# Eagle_LEDCUBE1.net
KiCad netlist of a schematic drawn in EAGLE
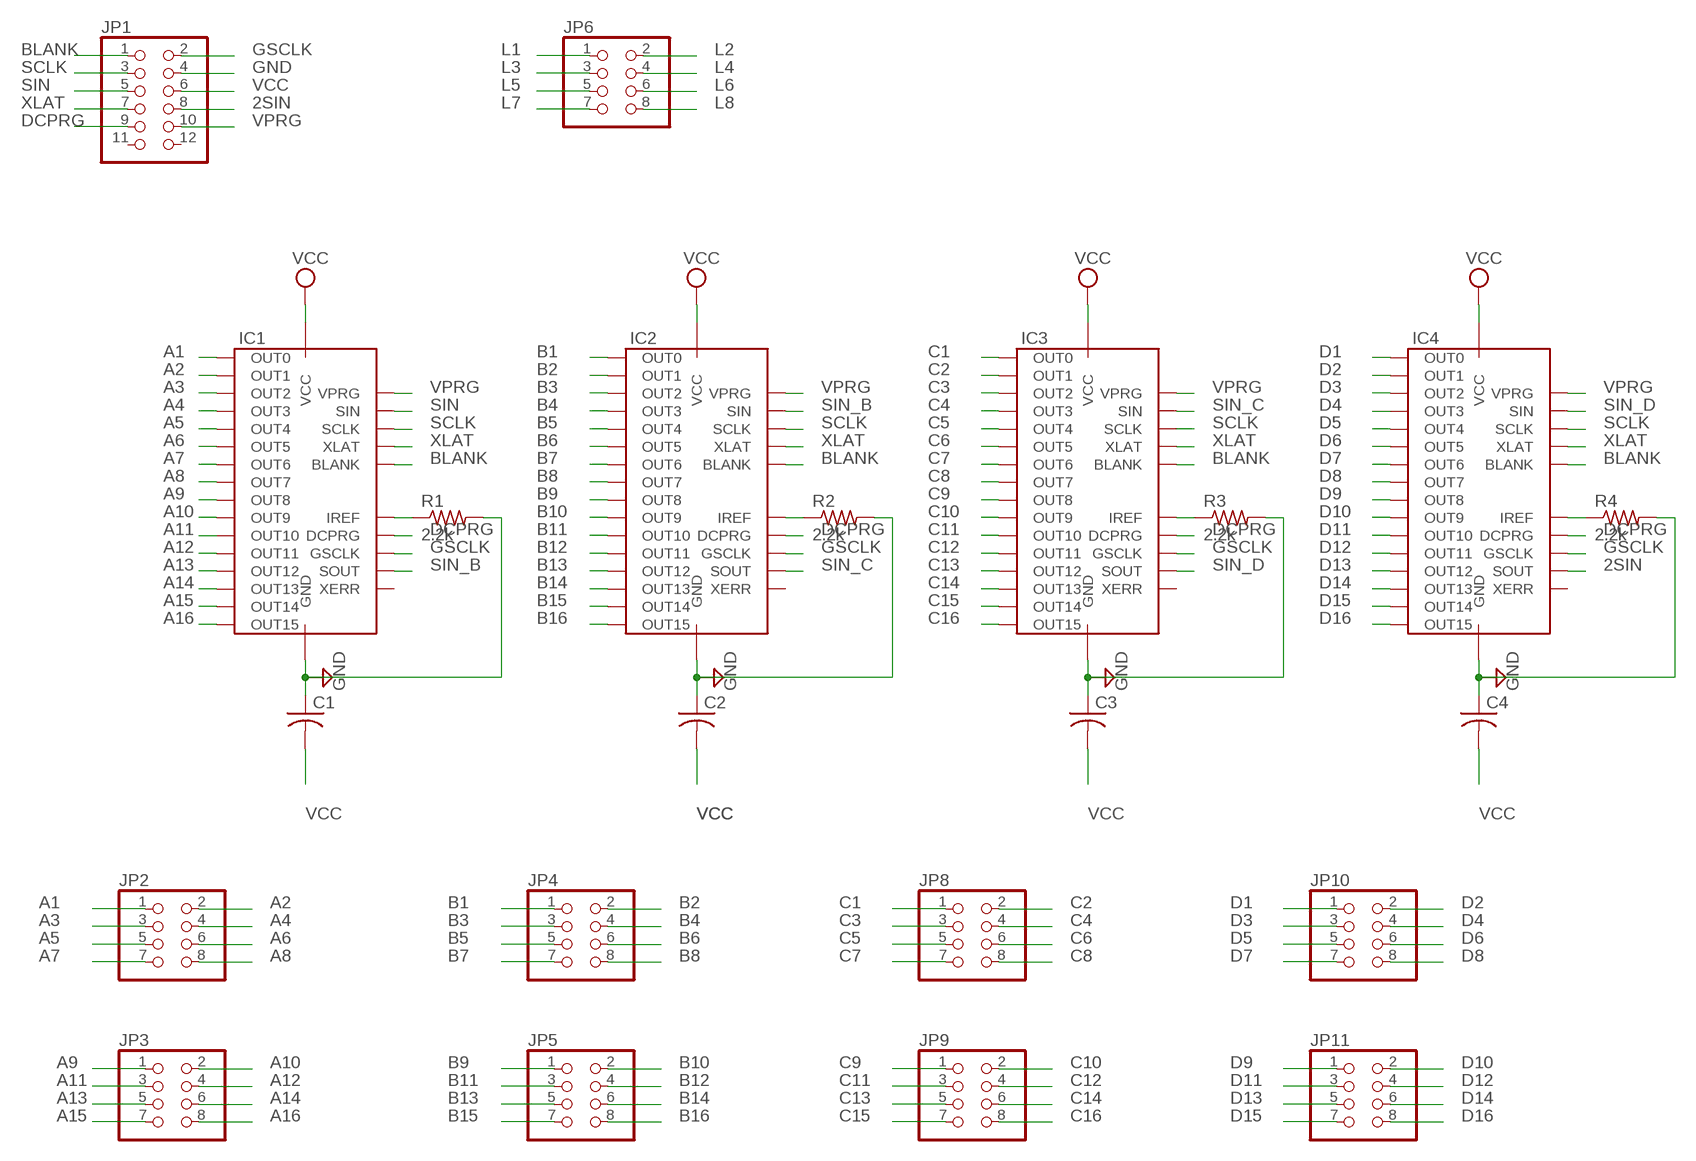
[diagram p0: schematic, sheet 1]
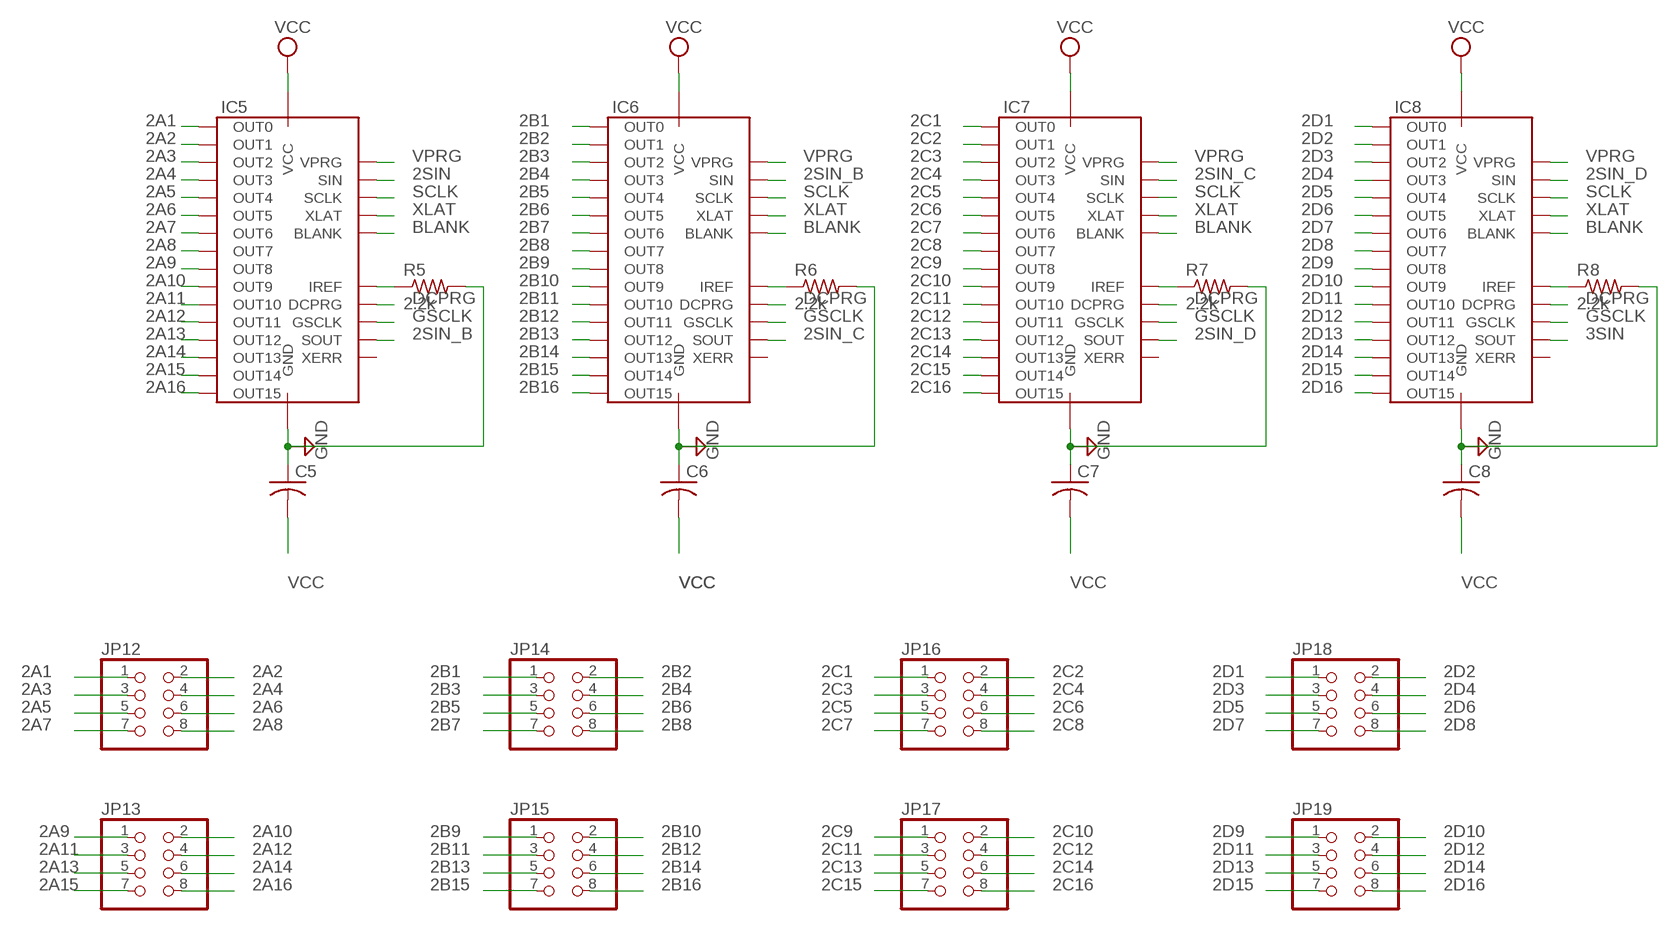
[diagram p1: schematic, sheet 2]
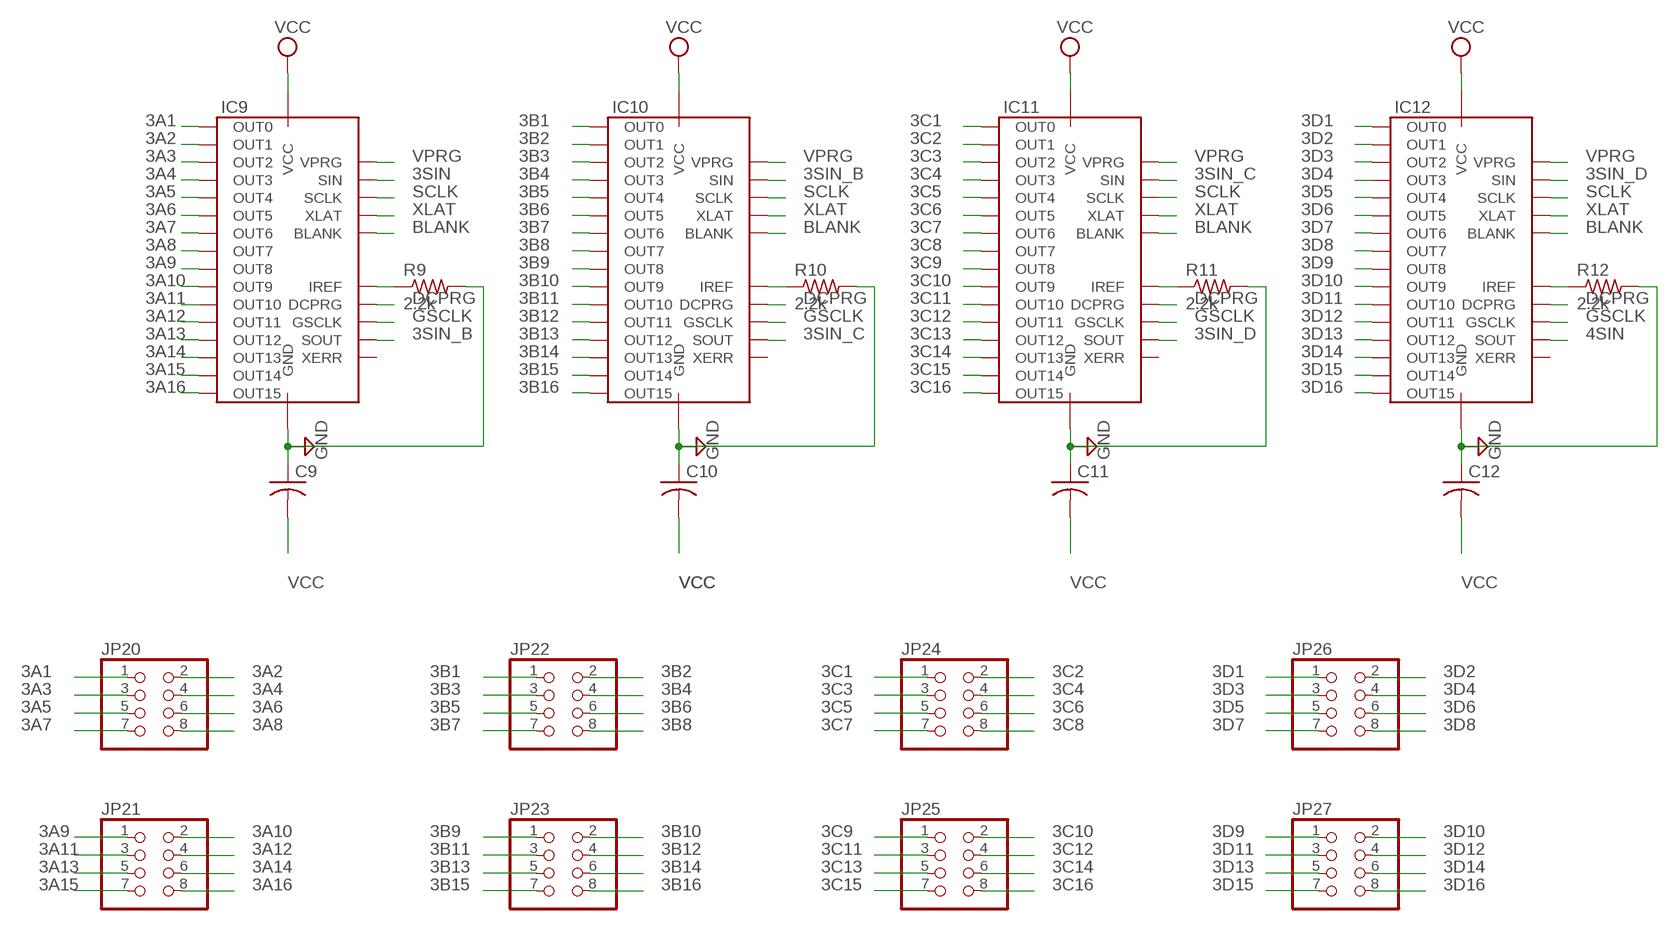
[diagram p2: schematic, sheet 3]
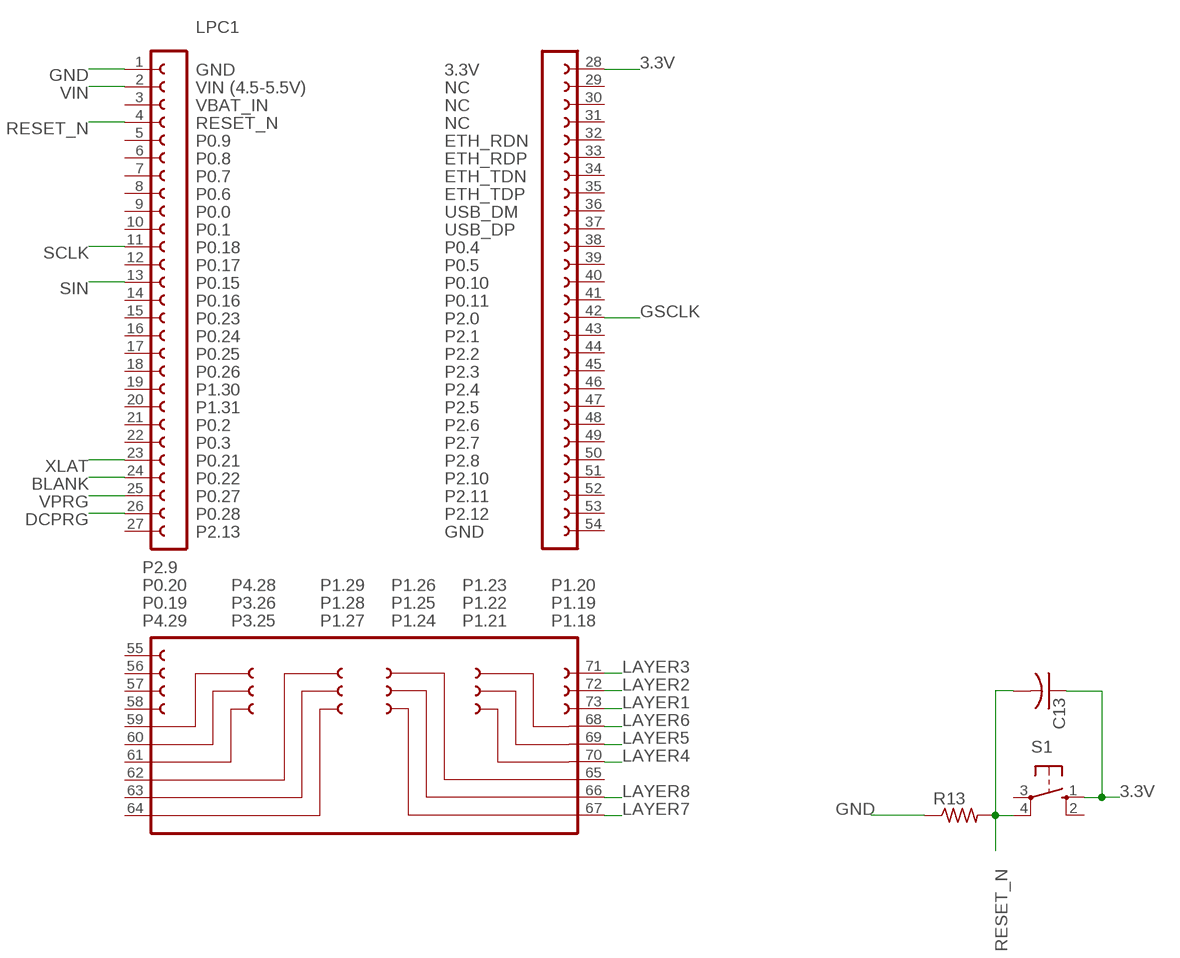
[diagram p3: schematic, sheet 4]
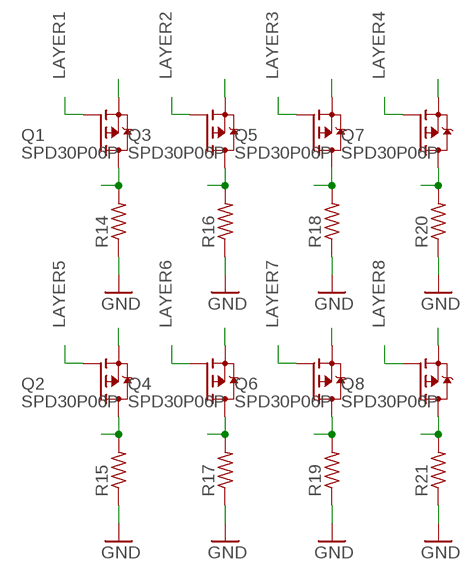
[diagram p4: schematic, sheet 5]

(export (version "E")
  (design (tool "Eeschema 10.0.6"))
  (components
    (comp (ref "C5")
      (value "C-USC0805K")
      (footprint "eagle-import:C0805K")
      (libsource (lib "eagle-import") (part "resistor_C-USC0805K"))
    )
    (comp (ref "C6")
      (value "C-USC0805K")
      (footprint "eagle-import:C0805K")
      (libsource (lib "eagle-import") (part "resistor_C-USC0805K"))
    )
    (comp (ref "C7")
      (value "C-USC0805K")
      (footprint "eagle-import:C0805K")
      (libsource (lib "eagle-import") (part "resistor_C-USC0805K"))
    )
    (comp (ref "C8")
      (value "C-USC0805K")
      (footprint "eagle-import:C0805K")
      (libsource (lib "eagle-import") (part "resistor_C-USC0805K"))
    )
    (comp (ref "IC5")
      (value "IC-PACKAGE_DIL28-1")
      (footprint "eagle-import:IC-SSOP28")
      (libsource (lib "eagle-import") (part "IC-PACKAGE_DIL28-1"))
    )
    (comp (ref "IC6")
      (value "IC-PACKAGE_DIL28-1")
      (footprint "eagle-import:IC-SSOP28")
      (libsource (lib "eagle-import") (part "IC-PACKAGE_DIL28-1"))
    )
    (comp (ref "IC7")
      (value "IC-PACKAGE_DIL28-1")
      (footprint "eagle-import:IC-SSOP28")
      (libsource (lib "eagle-import") (part "IC-PACKAGE_DIL28-1"))
    )
    (comp (ref "IC8")
      (value "IC-PACKAGE_DIL28-1")
      (footprint "eagle-import:IC-SSOP28")
      (libsource (lib "eagle-import") (part "IC-PACKAGE_DIL28-1"))
    )
    (comp (ref "JP12")
      (value "PINHD-2X4")
      (footprint "eagle-import:2X04")
      (libsource (lib "eagle-import") (part "PINHD-2X4"))
    )
    (comp (ref "JP13")
      (value "PINHD-2X4")
      (footprint "eagle-import:2X04")
      (libsource (lib "eagle-import") (part "PINHD-2X4"))
    )
    (comp (ref "JP14")
      (value "PINHD-2X4")
      (footprint "eagle-import:2X04")
      (libsource (lib "eagle-import") (part "PINHD-2X4"))
    )
    (comp (ref "JP15")
      (value "PINHD-2X4")
      (footprint "eagle-import:2X04")
      (libsource (lib "eagle-import") (part "PINHD-2X4"))
    )
    (comp (ref "JP16")
      (value "PINHD-2X4")
      (footprint "eagle-import:2X04")
      (libsource (lib "eagle-import") (part "PINHD-2X4"))
    )
    (comp (ref "JP17")
      (value "PINHD-2X4")
      (footprint "eagle-import:2X04")
      (libsource (lib "eagle-import") (part "PINHD-2X4"))
    )
    (comp (ref "JP18")
      (value "PINHD-2X4")
      (footprint "eagle-import:2X04")
      (libsource (lib "eagle-import") (part "PINHD-2X4"))
    )
    (comp (ref "JP19")
      (value "PINHD-2X4")
      (footprint "eagle-import:2X04")
      (libsource (lib "eagle-import") (part "PINHD-2X4"))
    )
    (comp (ref "R5")
      (value "2.2k")
      (footprint "eagle-import:R0805")
      (libsource (lib "eagle-import") (part "resistor_R-US_R0805"))
    )
    (comp (ref "R6")
      (value "2.2k")
      (footprint "eagle-import:R0805")
      (libsource (lib "eagle-import") (part "resistor_R-US_R0805"))
    )
    (comp (ref "R7")
      (value "2.2k")
      (footprint "eagle-import:R0805")
      (libsource (lib "eagle-import") (part "resistor_R-US_R0805"))
    )
    (comp (ref "R8")
      (value "2.2k")
      (footprint "eagle-import:R0805")
      (libsource (lib "eagle-import") (part "resistor_R-US_R0805"))
    )
    (comp (ref "Q1")
      (value "SPD30P06P")
      (footprint "eagle-import:TO251AA")
      (libsource (lib "eagle-import") (part "SPD30P06P"))
    )
    (comp (ref "Q2")
      (value "SPD30P06P")
      (footprint "eagle-import:TO251AA")
      (libsource (lib "eagle-import") (part "SPD30P06P"))
    )
    (comp (ref "Q3")
      (value "SPD30P06P")
      (footprint "eagle-import:TO251AA")
      (libsource (lib "eagle-import") (part "SPD30P06P"))
    )
    (comp (ref "Q4")
      (value "SPD30P06P")
      (footprint "eagle-import:TO251AA")
      (libsource (lib "eagle-import") (part "SPD30P06P"))
    )
    (comp (ref "Q5")
      (value "SPD30P06P")
      (footprint "eagle-import:TO251AA")
      (libsource (lib "eagle-import") (part "SPD30P06P"))
    )
    (comp (ref "Q6")
      (value "SPD30P06P")
      (footprint "eagle-import:TO251AA")
      (libsource (lib "eagle-import") (part "SPD30P06P"))
    )
    (comp (ref "Q7")
      (value "SPD30P06P")
      (footprint "eagle-import:TO251AA")
      (libsource (lib "eagle-import") (part "SPD30P06P"))
    )
    (comp (ref "Q8")
      (value "SPD30P06P")
      (footprint "eagle-import:TO251AA")
      (libsource (lib "eagle-import") (part "SPD30P06P"))
    )
    (comp (ref "R14")
      (value "R-US_R0805")
      (footprint "eagle-import:R0805")
      (libsource (lib "eagle-import") (part "resistor_R-US_R0805"))
    )
    (comp (ref "R15")
      (value "R-US_R0805")
      (footprint "eagle-import:R0805")
      (libsource (lib "eagle-import") (part "resistor_R-US_R0805"))
    )
    (comp (ref "R16")
      (value "R-US_R0805")
      (footprint "eagle-import:R0805")
      (libsource (lib "eagle-import") (part "resistor_R-US_R0805"))
    )
    (comp (ref "R17")
      (value "R-US_R0805")
      (footprint "eagle-import:R0805")
      (libsource (lib "eagle-import") (part "resistor_R-US_R0805"))
    )
    (comp (ref "R18")
      (value "R-US_R0805")
      (footprint "eagle-import:R0805")
      (libsource (lib "eagle-import") (part "resistor_R-US_R0805"))
    )
    (comp (ref "R19")
      (value "R-US_R0805")
      (footprint "eagle-import:R0805")
      (libsource (lib "eagle-import") (part "resistor_R-US_R0805"))
    )
    (comp (ref "R20")
      (value "R-US_R0805")
      (footprint "eagle-import:R0805")
      (libsource (lib "eagle-import") (part "resistor_R-US_R0805"))
    )
    (comp (ref "R21")
      (value "R-US_R0805")
      (footprint "eagle-import:R0805")
      (libsource (lib "eagle-import") (part "resistor_R-US_R0805"))
    )
    (comp (ref "C1")
      (value "C-USC0805K")
      (footprint "eagle-import:C0805K")
      (libsource (lib "eagle-import") (part "resistor_C-USC0805K"))
    )
    (comp (ref "C2")
      (value "C-USC0805K")
      (footprint "eagle-import:C0805K")
      (libsource (lib "eagle-import") (part "resistor_C-USC0805K"))
    )
    (comp (ref "C3")
      (value "C-USC0805K")
      (footprint "eagle-import:C0805K")
      (libsource (lib "eagle-import") (part "resistor_C-USC0805K"))
    )
    (comp (ref "C4")
      (value "C-USC0805K")
      (footprint "eagle-import:C0805K")
      (libsource (lib "eagle-import") (part "resistor_C-USC0805K"))
    )
    (comp (ref "IC1")
      (value "IC-PACKAGE_DIL28-1")
      (footprint "eagle-import:IC-SSOP28")
      (libsource (lib "eagle-import") (part "IC-PACKAGE_DIL28-1"))
    )
    (comp (ref "IC2")
      (value "IC-PACKAGE_DIL28-1")
      (footprint "eagle-import:IC-SSOP28")
      (libsource (lib "eagle-import") (part "IC-PACKAGE_DIL28-1"))
    )
    (comp (ref "IC3")
      (value "IC-PACKAGE_DIL28-1")
      (footprint "eagle-import:IC-SSOP28")
      (libsource (lib "eagle-import") (part "IC-PACKAGE_DIL28-1"))
    )
    (comp (ref "IC4")
      (value "IC-PACKAGE_DIL28-1")
      (footprint "eagle-import:IC-SSOP28")
      (libsource (lib "eagle-import") (part "IC-PACKAGE_DIL28-1"))
    )
    (comp (ref "JP1")
      (value "PINHD-2X6")
      (footprint "eagle-import:2X06")
      (libsource (lib "eagle-import") (part "PINHD-2X6"))
    )
    (comp (ref "JP2")
      (value "PINHD-2X4")
      (footprint "eagle-import:2X04")
      (libsource (lib "eagle-import") (part "PINHD-2X4"))
    )
    (comp (ref "JP3")
      (value "PINHD-2X4")
      (footprint "eagle-import:2X04")
      (libsource (lib "eagle-import") (part "PINHD-2X4"))
    )
    (comp (ref "JP4")
      (value "PINHD-2X4")
      (footprint "eagle-import:2X04")
      (libsource (lib "eagle-import") (part "PINHD-2X4"))
    )
    (comp (ref "JP5")
      (value "PINHD-2X4")
      (footprint "eagle-import:2X04")
      (libsource (lib "eagle-import") (part "PINHD-2X4"))
    )
    (comp (ref "JP6")
      (value "PINHD-2X4")
      (footprint "eagle-import:2X04")
      (libsource (lib "eagle-import") (part "PINHD-2X4"))
    )
    (comp (ref "JP8")
      (value "PINHD-2X4")
      (footprint "eagle-import:2X04")
      (libsource (lib "eagle-import") (part "PINHD-2X4"))
    )
    (comp (ref "JP9")
      (value "PINHD-2X4")
      (footprint "eagle-import:2X04")
      (libsource (lib "eagle-import") (part "PINHD-2X4"))
    )
    (comp (ref "JP10")
      (value "PINHD-2X4")
      (footprint "eagle-import:2X04")
      (libsource (lib "eagle-import") (part "PINHD-2X4"))
    )
    (comp (ref "JP11")
      (value "PINHD-2X4")
      (footprint "eagle-import:2X04")
      (libsource (lib "eagle-import") (part "PINHD-2X4"))
    )
    (comp (ref "R1")
      (value "2.2k")
      (footprint "eagle-import:R0805")
      (libsource (lib "eagle-import") (part "resistor_R-US_R0805"))
    )
    (comp (ref "R2")
      (value "2.2k")
      (footprint "eagle-import:R0805")
      (libsource (lib "eagle-import") (part "resistor_R-US_R0805"))
    )
    (comp (ref "R3")
      (value "2.2k")
      (footprint "eagle-import:R0805")
      (libsource (lib "eagle-import") (part "resistor_R-US_R0805"))
    )
    (comp (ref "R4")
      (value "2.2k")
      (footprint "eagle-import:R0805")
      (libsource (lib "eagle-import") (part "resistor_R-US_R0805"))
    )
    (comp (ref "C13")
      (value "C-USC0805K")
      (footprint "eagle-import:C0805K")
      (libsource (lib "eagle-import") (part "C-USC0805K"))
    )
    (comp (ref "LPC1")
      (value "LPCXPRESSO_LPC1769")
      (footprint "eagle-import:LPCXPRESSO_LPC1769")
      (libsource (lib "eagle-import") (part "LPCXPRESSO_LPC1769"))
    )
    (comp (ref "R13")
      (value "R-US_R0805")
      (footprint "eagle-import:R0805")
      (libsource (lib "eagle-import") (part "R-US_R0805"))
    )
    (comp (ref "S1")
      (value "10-XX")
      (footprint "eagle-import:B3F-10XX")
      (fields (field (name "MPN") "B3F-1000"))
      (libsource (lib "eagle-import") (part "10-XX"))
    )
    (comp (ref "C9")
      (value "C-USC0805K")
      (footprint "eagle-import:C0805K")
      (libsource (lib "eagle-import") (part "resistor_C-USC0805K"))
    )
    (comp (ref "C10")
      (value "C-USC0805K")
      (footprint "eagle-import:C0805K")
      (libsource (lib "eagle-import") (part "resistor_C-USC0805K"))
    )
    (comp (ref "C11")
      (value "C-USC0805K")
      (footprint "eagle-import:C0805K")
      (libsource (lib "eagle-import") (part "resistor_C-USC0805K"))
    )
    (comp (ref "C12")
      (value "C-USC0805K")
      (footprint "eagle-import:C0805K")
      (libsource (lib "eagle-import") (part "resistor_C-USC0805K"))
    )
    (comp (ref "IC9")
      (value "IC-PACKAGE_DIL28-1")
      (footprint "eagle-import:IC-SSOP28")
      (libsource (lib "eagle-import") (part "IC-PACKAGE_DIL28-1"))
    )
    (comp (ref "IC10")
      (value "IC-PACKAGE_DIL28-1")
      (footprint "eagle-import:IC-SSOP28")
      (libsource (lib "eagle-import") (part "IC-PACKAGE_DIL28-1"))
    )
    (comp (ref "IC11")
      (value "IC-PACKAGE_DIL28-1")
      (footprint "eagle-import:IC-SSOP28")
      (libsource (lib "eagle-import") (part "IC-PACKAGE_DIL28-1"))
    )
    (comp (ref "IC12")
      (value "IC-PACKAGE_DIL28-1")
      (footprint "eagle-import:IC-SSOP28")
      (libsource (lib "eagle-import") (part "IC-PACKAGE_DIL28-1"))
    )
    (comp (ref "JP20")
      (value "PINHD-2X4")
      (footprint "eagle-import:2X04")
      (libsource (lib "eagle-import") (part "PINHD-2X4"))
    )
    (comp (ref "JP21")
      (value "PINHD-2X4")
      (footprint "eagle-import:2X04")
      (libsource (lib "eagle-import") (part "PINHD-2X4"))
    )
    (comp (ref "JP22")
      (value "PINHD-2X4")
      (footprint "eagle-import:2X04")
      (libsource (lib "eagle-import") (part "PINHD-2X4"))
    )
    (comp (ref "JP23")
      (value "PINHD-2X4")
      (footprint "eagle-import:2X04")
      (libsource (lib "eagle-import") (part "PINHD-2X4"))
    )
    (comp (ref "JP24")
      (value "PINHD-2X4")
      (footprint "eagle-import:2X04")
      (libsource (lib "eagle-import") (part "PINHD-2X4"))
    )
    (comp (ref "JP25")
      (value "PINHD-2X4")
      (footprint "eagle-import:2X04")
      (libsource (lib "eagle-import") (part "PINHD-2X4"))
    )
    (comp (ref "JP26")
      (value "PINHD-2X4")
      (footprint "eagle-import:2X04")
      (libsource (lib "eagle-import") (part "PINHD-2X4"))
    )
    (comp (ref "JP27")
      (value "PINHD-2X4")
      (footprint "eagle-import:2X04")
      (libsource (lib "eagle-import") (part "PINHD-2X4"))
    )
    (comp (ref "R9")
      (value "2.2k")
      (footprint "eagle-import:R0805")
      (libsource (lib "eagle-import") (part "resistor_R-US_R0805"))
    )
    (comp (ref "R10")
      (value "2.2k")
      (footprint "eagle-import:R0805")
      (libsource (lib "eagle-import") (part "resistor_R-US_R0805"))
    )
    (comp (ref "R11")
      (value "2.2k")
      (footprint "eagle-import:R0805")
      (libsource (lib "eagle-import") (part "resistor_R-US_R0805"))
    )
    (comp (ref "R12")
      (value "2.2k")
      (footprint "eagle-import:R0805")
      (libsource (lib "eagle-import") (part "resistor_R-US_R0805"))
    )
  )
  (nets
    (net (code "1") (name "2A1") (class "Default")
      (node (ref "IC5") (pin "7") (pinfunction "OUT0_7") (pintype "open_collector"))
      (node (ref "JP12") (pin "1") (pinfunction "1_1") (pintype "passive"))
    )
    (net (code "2") (name "2A2") (class "Default")
      (node (ref "IC5") (pin "8") (pinfunction "OUT1_8") (pintype "open_collector"))
      (node (ref "JP12") (pin "2") (pinfunction "2_2") (pintype "passive"))
    )
    (net (code "3") (name "2A3") (class "Default")
      (node (ref "IC5") (pin "9") (pinfunction "OUT2_9") (pintype "open_collector"))
      (node (ref "JP12") (pin "3") (pinfunction "3_3") (pintype "passive"))
    )
    (net (code "4") (name "2A4") (class "Default")
      (node (ref "IC5") (pin "10") (pinfunction "OUT3_10") (pintype "open_collector"))
      (node (ref "JP12") (pin "4") (pinfunction "4_4") (pintype "passive"))
    )
    (net (code "5") (name "2A5") (class "Default")
      (node (ref "IC5") (pin "11") (pinfunction "OUT4_11") (pintype "open_collector"))
      (node (ref "JP12") (pin "5") (pinfunction "5_5") (pintype "passive"))
    )
    (net (code "6") (name "2A6") (class "Default")
      (node (ref "IC5") (pin "12") (pinfunction "OUT5_12") (pintype "open_collector"))
      (node (ref "JP12") (pin "6") (pinfunction "6_6") (pintype "passive"))
    )
    (net (code "7") (name "2A7") (class "Default")
      (node (ref "IC5") (pin "13") (pinfunction "OUT6_13") (pintype "open_collector"))
      (node (ref "JP12") (pin "7") (pinfunction "7_7") (pintype "passive"))
    )
    (net (code "8") (name "2A8") (class "Default")
      (node (ref "IC5") (pin "14") (pinfunction "OUT7_14") (pintype "open_collector"))
      (node (ref "JP12") (pin "8") (pinfunction "8_8") (pintype "passive"))
    )
    (net (code "9") (name "2A9") (class "Default")
      (node (ref "IC5") (pin "15") (pinfunction "OUT8_15") (pintype "open_collector"))
      (node (ref "JP13") (pin "1") (pinfunction "1_1") (pintype "passive"))
    )
    (net (code "10") (name "2A10") (class "Default")
      (node (ref "IC5") (pin "16") (pinfunction "OUT9_16") (pintype "open_collector"))
      (node (ref "JP13") (pin "2") (pinfunction "2_2") (pintype "passive"))
    )
    (net (code "11") (name "2A11") (class "Default")
      (node (ref "IC5") (pin "17") (pinfunction "OUT10_17") (pintype "open_collector"))
      (node (ref "JP13") (pin "3") (pinfunction "3_3") (pintype "passive"))
    )
    (net (code "12") (name "2A12") (class "Default")
      (node (ref "IC5") (pin "18") (pinfunction "OUT11_18") (pintype "open_collector"))
      (node (ref "JP13") (pin "4") (pinfunction "4_4") (pintype "passive"))
    )
    (net (code "13") (name "2A13") (class "Default")
      (node (ref "IC5") (pin "19") (pinfunction "OUT12_19") (pintype "open_collector"))
      (node (ref "JP13") (pin "5") (pinfunction "5_5") (pintype "passive"))
    )
    (net (code "14") (name "2A14") (class "Default")
      (node (ref "IC5") (pin "20") (pinfunction "OUT13_20") (pintype "open_collector"))
      (node (ref "JP13") (pin "6") (pinfunction "6_6") (pintype "passive"))
    )
    (net (code "15") (name "2A15") (class "Default")
      (node (ref "IC5") (pin "21") (pinfunction "OUT14_21") (pintype "open_collector"))
      (node (ref "JP13") (pin "7") (pinfunction "7_7") (pintype "passive"))
    )
    (net (code "16") (name "2A16") (class "Default")
      (node (ref "IC5") (pin "22") (pinfunction "OUT15_22") (pintype "open_collector"))
      (node (ref "JP13") (pin "8") (pinfunction "8_8") (pintype "passive"))
    )
    (net (code "17") (name "2B1") (class "Default")
      (node (ref "IC6") (pin "7") (pinfunction "OUT0_7") (pintype "open_collector"))
      (node (ref "JP14") (pin "1") (pinfunction "1_1") (pintype "passive"))
    )
    (net (code "18") (name "2B2") (class "Default")
      (node (ref "IC6") (pin "8") (pinfunction "OUT1_8") (pintype "open_collector"))
      (node (ref "JP14") (pin "2") (pinfunction "2_2") (pintype "passive"))
    )
    (net (code "19") (name "2B3") (class "Default")
      (node (ref "IC6") (pin "9") (pinfunction "OUT2_9") (pintype "open_collector"))
      (node (ref "JP14") (pin "3") (pinfunction "3_3") (pintype "passive"))
    )
    (net (code "20") (name "2B4") (class "Default")
      (node (ref "IC6") (pin "10") (pinfunction "OUT3_10") (pintype "open_collector"))
      (node (ref "JP14") (pin "4") (pinfunction "4_4") (pintype "passive"))
    )
    (net (code "21") (name "2B5") (class "Default")
      (node (ref "IC6") (pin "11") (pinfunction "OUT4_11") (pintype "open_collector"))
      (node (ref "JP14") (pin "5") (pinfunction "5_5") (pintype "passive"))
    )
    (net (code "22") (name "2B6") (class "Default")
      (node (ref "IC6") (pin "12") (pinfunction "OUT5_12") (pintype "open_collector"))
      (node (ref "JP14") (pin "6") (pinfunction "6_6") (pintype "passive"))
    )
    (net (code "23") (name "2B7") (class "Default")
      (node (ref "IC6") (pin "13") (pinfunction "OUT6_13") (pintype "open_collector"))
      (node (ref "JP14") (pin "7") (pinfunction "7_7") (pintype "passive"))
    )
    (net (code "24") (name "2B8") (class "Default")
      (node (ref "IC6") (pin "14") (pinfunction "OUT7_14") (pintype "open_collector"))
      (node (ref "JP14") (pin "8") (pinfunction "8_8") (pintype "passive"))
    )
    (net (code "25") (name "2B9") (class "Default")
      (node (ref "IC6") (pin "15") (pinfunction "OUT8_15") (pintype "open_collector"))
      (node (ref "JP15") (pin "1") (pinfunction "1_1") (pintype "passive"))
    )
    (net (code "26") (name "2B10") (class "Default")
      (node (ref "IC6") (pin "16") (pinfunction "OUT9_16") (pintype "open_collector"))
      (node (ref "JP15") (pin "2") (pinfunction "2_2") (pintype "passive"))
    )
    (net (code "27") (name "2B11") (class "Default")
      (node (ref "IC6") (pin "17") (pinfunction "OUT10_17") (pintype "open_collector"))
      (node (ref "JP15") (pin "3") (pinfunction "3_3") (pintype "passive"))
    )
    (net (code "28") (name "2B12") (class "Default")
      (node (ref "IC6") (pin "18") (pinfunction "OUT11_18") (pintype "open_collector"))
      (node (ref "JP15") (pin "4") (pinfunction "4_4") (pintype "passive"))
    )
    (net (code "29") (name "2B13") (class "Default")
      (node (ref "IC6") (pin "19") (pinfunction "OUT12_19") (pintype "open_collector"))
      (node (ref "JP15") (pin "5") (pinfunction "5_5") (pintype "passive"))
    )
    (net (code "30") (name "2B14") (class "Default")
      (node (ref "IC6") (pin "20") (pinfunction "OUT13_20") (pintype "open_collector"))
      (node (ref "JP15") (pin "6") (pinfunction "6_6") (pintype "passive"))
    )
    (net (code "31") (name "2B15") (class "Default")
      (node (ref "IC6") (pin "21") (pinfunction "OUT14_21") (pintype "open_collector"))
      (node (ref "JP15") (pin "7") (pinfunction "7_7") (pintype "passive"))
    )
    (net (code "32") (name "2B16") (class "Default")
      (node (ref "IC6") (pin "22") (pinfunction "OUT15_22") (pintype "open_collector"))
      (node (ref "JP15") (pin "8") (pinfunction "8_8") (pintype "passive"))
    )
    (net (code "33") (name "2C1") (class "Default")
      (node (ref "IC7") (pin "7") (pinfunction "OUT0_7") (pintype "open_collector"))
      (node (ref "JP16") (pin "1") (pinfunction "1_1") (pintype "passive"))
    )
    (net (code "34") (name "2C2") (class "Default")
      (node (ref "IC7") (pin "8") (pinfunction "OUT1_8") (pintype "open_collector"))
      (node (ref "JP16") (pin "2") (pinfunction "2_2") (pintype "passive"))
    )
    (net (code "35") (name "2C3") (class "Default")
      (node (ref "IC7") (pin "9") (pinfunction "OUT2_9") (pintype "open_collector"))
      (node (ref "JP16") (pin "3") (pinfunction "3_3") (pintype "passive"))
    )
    (net (code "36") (name "2C4") (class "Default")
      (node (ref "IC7") (pin "10") (pinfunction "OUT3_10") (pintype "open_collector"))
      (node (ref "JP16") (pin "4") (pinfunction "4_4") (pintype "passive"))
    )
    (net (code "37") (name "2C5") (class "Default")
      (node (ref "IC7") (pin "11") (pinfunction "OUT4_11") (pintype "open_collector"))
      (node (ref "JP16") (pin "5") (pinfunction "5_5") (pintype "passive"))
    )
    (net (code "38") (name "2C6") (class "Default")
      (node (ref "IC7") (pin "12") (pinfunction "OUT5_12") (pintype "open_collector"))
      (node (ref "JP16") (pin "6") (pinfunction "6_6") (pintype "passive"))
    )
    (net (code "39") (name "2C7") (class "Default")
      (node (ref "IC7") (pin "13") (pinfunction "OUT6_13") (pintype "open_collector"))
      (node (ref "JP16") (pin "7") (pinfunction "7_7") (pintype "passive"))
    )
    (net (code "40") (name "2C8") (class "Default")
      (node (ref "IC7") (pin "14") (pinfunction "OUT7_14") (pintype "open_collector"))
      (node (ref "JP16") (pin "8") (pinfunction "8_8") (pintype "passive"))
    )
    (net (code "41") (name "2C9") (class "Default")
      (node (ref "IC7") (pin "15") (pinfunction "OUT8_15") (pintype "open_collector"))
      (node (ref "JP17") (pin "1") (pinfunction "1_1") (pintype "passive"))
    )
    (net (code "42") (name "2C10") (class "Default")
      (node (ref "IC7") (pin "16") (pinfunction "OUT9_16") (pintype "open_collector"))
      (node (ref "JP17") (pin "2") (pinfunction "2_2") (pintype "passive"))
    )
    (net (code "43") (name "2C11") (class "Default")
      (node (ref "IC7") (pin "17") (pinfunction "OUT10_17") (pintype "open_collector"))
      (node (ref "JP17") (pin "3") (pinfunction "3_3") (pintype "passive"))
    )
    (net (code "44") (name "2C12") (class "Default")
      (node (ref "IC7") (pin "18") (pinfunction "OUT11_18") (pintype "open_collector"))
      (node (ref "JP17") (pin "4") (pinfunction "4_4") (pintype "passive"))
    )
    (net (code "45") (name "2C13") (class "Default")
      (node (ref "IC7") (pin "19") (pinfunction "OUT12_19") (pintype "open_collector"))
      (node (ref "JP17") (pin "5") (pinfunction "5_5") (pintype "passive"))
    )
    (net (code "46") (name "2C14") (class "Default")
      (node (ref "IC7") (pin "20") (pinfunction "OUT13_20") (pintype "open_collector"))
      (node (ref "JP17") (pin "6") (pinfunction "6_6") (pintype "passive"))
    )
    (net (code "47") (name "2C15") (class "Default")
      (node (ref "IC7") (pin "21") (pinfunction "OUT14_21") (pintype "open_collector"))
      (node (ref "JP17") (pin "7") (pinfunction "7_7") (pintype "passive"))
    )
    (net (code "48") (name "2C16") (class "Default")
      (node (ref "IC7") (pin "22") (pinfunction "OUT15_22") (pintype "open_collector"))
      (node (ref "JP17") (pin "8") (pinfunction "8_8") (pintype "passive"))
    )
    (net (code "49") (name "2D1") (class "Default")
      (node (ref "IC8") (pin "7") (pinfunction "OUT0_7") (pintype "open_collector"))
      (node (ref "JP18") (pin "1") (pinfunction "1_1") (pintype "passive"))
    )
    (net (code "50") (name "2D2") (class "Default")
      (node (ref "IC8") (pin "8") (pinfunction "OUT1_8") (pintype "open_collector"))
      (node (ref "JP18") (pin "2") (pinfunction "2_2") (pintype "passive"))
    )
    (net (code "51") (name "2D3") (class "Default")
      (node (ref "IC8") (pin "9") (pinfunction "OUT2_9") (pintype "open_collector"))
      (node (ref "JP18") (pin "3") (pinfunction "3_3") (pintype "passive"))
    )
    (net (code "52") (name "2D4") (class "Default")
      (node (ref "IC8") (pin "10") (pinfunction "OUT3_10") (pintype "open_collector"))
      (node (ref "JP18") (pin "4") (pinfunction "4_4") (pintype "passive"))
    )
    (net (code "53") (name "2D5") (class "Default")
      (node (ref "IC8") (pin "11") (pinfunction "OUT4_11") (pintype "open_collector"))
      (node (ref "JP18") (pin "5") (pinfunction "5_5") (pintype "passive"))
    )
    (net (code "54") (name "2D6") (class "Default")
      (node (ref "IC8") (pin "12") (pinfunction "OUT5_12") (pintype "open_collector"))
      (node (ref "JP18") (pin "6") (pinfunction "6_6") (pintype "passive"))
    )
    (net (code "55") (name "2D7") (class "Default")
      (node (ref "IC8") (pin "13") (pinfunction "OUT6_13") (pintype "open_collector"))
      (node (ref "JP18") (pin "7") (pinfunction "7_7") (pintype "passive"))
    )
    (net (code "56") (name "2D8") (class "Default")
      (node (ref "IC8") (pin "14") (pinfunction "OUT7_14") (pintype "open_collector"))
      (node (ref "JP18") (pin "8") (pinfunction "8_8") (pintype "passive"))
    )
    (net (code "57") (name "2D9") (class "Default")
      (node (ref "IC8") (pin "15") (pinfunction "OUT8_15") (pintype "open_collector"))
      (node (ref "JP19") (pin "1") (pinfunction "1_1") (pintype "passive"))
    )
    (net (code "58") (name "2D10") (class "Default")
      (node (ref "IC8") (pin "16") (pinfunction "OUT9_16") (pintype "open_collector"))
      (node (ref "JP19") (pin "2") (pinfunction "2_2") (pintype "passive"))
    )
    (net (code "59") (name "2D11") (class "Default")
      (node (ref "IC8") (pin "17") (pinfunction "OUT10_17") (pintype "open_collector"))
      (node (ref "JP19") (pin "3") (pinfunction "3_3") (pintype "passive"))
    )
    (net (code "60") (name "2D12") (class "Default")
      (node (ref "IC8") (pin "18") (pinfunction "OUT11_18") (pintype "open_collector"))
      (node (ref "JP19") (pin "4") (pinfunction "4_4") (pintype "passive"))
    )
    (net (code "61") (name "2D13") (class "Default")
      (node (ref "IC8") (pin "19") (pinfunction "OUT12_19") (pintype "open_collector"))
      (node (ref "JP19") (pin "5") (pinfunction "5_5") (pintype "passive"))
    )
    (net (code "62") (name "2D14") (class "Default")
      (node (ref "IC8") (pin "20") (pinfunction "OUT13_20") (pintype "open_collector"))
      (node (ref "JP19") (pin "6") (pinfunction "6_6") (pintype "passive"))
    )
    (net (code "63") (name "2D15") (class "Default")
      (node (ref "IC8") (pin "21") (pinfunction "OUT14_21") (pintype "open_collector"))
      (node (ref "JP19") (pin "7") (pinfunction "7_7") (pintype "passive"))
    )
    (net (code "64") (name "2D16") (class "Default")
      (node (ref "IC8") (pin "22") (pinfunction "OUT15_22") (pintype "open_collector"))
      (node (ref "JP19") (pin "8") (pinfunction "8_8") (pintype "passive"))
    )
    (net (code "65") (name "2SIN") (class "Default")
      (node (ref "IC4") (pin "24") (pinfunction "SOUT_24") (pintype "output"))
      (node (ref "IC5") (pin "5") (pinfunction "SIN_5") (pintype "input"))
      (node (ref "JP1") (pin "8") (pinfunction "8_8") (pintype "passive"))
    )
    (net (code "66") (name "2SIN_B") (class "Default")
      (node (ref "IC5") (pin "24") (pinfunction "SOUT_24") (pintype "output"))
      (node (ref "IC6") (pin "5") (pinfunction "SIN_5") (pintype "input"))
    )
    (net (code "67") (name "2SIN_C") (class "Default")
      (node (ref "IC6") (pin "24") (pinfunction "SOUT_24") (pintype "output"))
      (node (ref "IC7") (pin "5") (pinfunction "SIN_5") (pintype "input"))
    )
    (net (code "68") (name "2SIN_D") (class "Default")
      (node (ref "IC7") (pin "24") (pinfunction "SOUT_24") (pintype "output"))
      (node (ref "IC8") (pin "5") (pinfunction "SIN_5") (pintype "input"))
    )
    (net (code "69") (name "3.3V") (class "Default")
      (node (ref "C13") (pin "1") (pinfunction "1_1") (pintype "passive"))
      (node (ref "LPC1") (pin "28") (pinfunction "28_28") (pintype "passive"))
      (node (ref "S1") (pin "1") (pinfunction "S_1") (pintype "passive"))
    )
    (net (code "70") (name "3A1") (class "Default")
      (node (ref "IC9") (pin "7") (pinfunction "OUT0_7") (pintype "open_collector"))
      (node (ref "JP20") (pin "1") (pinfunction "1_1") (pintype "passive"))
    )
    (net (code "71") (name "3A2") (class "Default")
      (node (ref "IC9") (pin "8") (pinfunction "OUT1_8") (pintype "open_collector"))
      (node (ref "JP20") (pin "2") (pinfunction "2_2") (pintype "passive"))
    )
    (net (code "72") (name "3A3") (class "Default")
      (node (ref "IC9") (pin "9") (pinfunction "OUT2_9") (pintype "open_collector"))
      (node (ref "JP20") (pin "3") (pinfunction "3_3") (pintype "passive"))
    )
    (net (code "73") (name "3A4") (class "Default")
      (node (ref "IC9") (pin "10") (pinfunction "OUT3_10") (pintype "open_collector"))
      (node (ref "JP20") (pin "4") (pinfunction "4_4") (pintype "passive"))
    )
    (net (code "74") (name "3A5") (class "Default")
      (node (ref "IC9") (pin "11") (pinfunction "OUT4_11") (pintype "open_collector"))
      (node (ref "JP20") (pin "5") (pinfunction "5_5") (pintype "passive"))
    )
    (net (code "75") (name "3A6") (class "Default")
      (node (ref "IC9") (pin "12") (pinfunction "OUT5_12") (pintype "open_collector"))
      (node (ref "JP20") (pin "6") (pinfunction "6_6") (pintype "passive"))
    )
    (net (code "76") (name "3A7") (class "Default")
      (node (ref "IC9") (pin "13") (pinfunction "OUT6_13") (pintype "open_collector"))
      (node (ref "JP20") (pin "7") (pinfunction "7_7") (pintype "passive"))
    )
    (net (code "77") (name "3A8") (class "Default")
      (node (ref "IC9") (pin "14") (pinfunction "OUT7_14") (pintype "open_collector"))
      (node (ref "JP20") (pin "8") (pinfunction "8_8") (pintype "passive"))
    )
    (net (code "78") (name "3A9") (class "Default")
      (node (ref "IC9") (pin "15") (pinfunction "OUT8_15") (pintype "open_collector"))
      (node (ref "JP21") (pin "1") (pinfunction "1_1") (pintype "passive"))
    )
    (net (code "79") (name "3A10") (class "Default")
      (node (ref "IC9") (pin "16") (pinfunction "OUT9_16") (pintype "open_collector"))
      (node (ref "JP21") (pin "2") (pinfunction "2_2") (pintype "passive"))
    )
    (net (code "80") (name "3A11") (class "Default")
      (node (ref "IC9") (pin "17") (pinfunction "OUT10_17") (pintype "open_collector"))
      (node (ref "JP21") (pin "3") (pinfunction "3_3") (pintype "passive"))
    )
    (net (code "81") (name "3A12") (class "Default")
      (node (ref "IC9") (pin "18") (pinfunction "OUT11_18") (pintype "open_collector"))
      (node (ref "JP21") (pin "4") (pinfunction "4_4") (pintype "passive"))
    )
    (net (code "82") (name "3A13") (class "Default")
      (node (ref "IC9") (pin "19") (pinfunction "OUT12_19") (pintype "open_collector"))
      (node (ref "JP21") (pin "5") (pinfunction "5_5") (pintype "passive"))
    )
    (net (code "83") (name "3A14") (class "Default")
      (node (ref "IC9") (pin "20") (pinfunction "OUT13_20") (pintype "open_collector"))
      (node (ref "JP21") (pin "6") (pinfunction "6_6") (pintype "passive"))
    )
    (net (code "84") (name "3A15") (class "Default")
      (node (ref "IC9") (pin "21") (pinfunction "OUT14_21") (pintype "open_collector"))
      (node (ref "JP21") (pin "7") (pinfunction "7_7") (pintype "passive"))
    )
    (net (code "85") (name "3A16") (class "Default")
      (node (ref "IC9") (pin "22") (pinfunction "OUT15_22") (pintype "open_collector"))
      (node (ref "JP21") (pin "8") (pinfunction "8_8") (pintype "passive"))
    )
    (net (code "86") (name "3B1") (class "Default")
      (node (ref "IC10") (pin "7") (pinfunction "OUT0_7") (pintype "open_collector"))
      (node (ref "JP22") (pin "1") (pinfunction "1_1") (pintype "passive"))
    )
    (net (code "87") (name "3B2") (class "Default")
      (node (ref "IC10") (pin "8") (pinfunction "OUT1_8") (pintype "open_collector"))
      (node (ref "JP22") (pin "2") (pinfunction "2_2") (pintype "passive"))
    )
    (net (code "88") (name "3B3") (class "Default")
      (node (ref "IC10") (pin "9") (pinfunction "OUT2_9") (pintype "open_collector"))
      (node (ref "JP22") (pin "3") (pinfunction "3_3") (pintype "passive"))
    )
    (net (code "89") (name "3B4") (class "Default")
      (node (ref "IC10") (pin "10") (pinfunction "OUT3_10") (pintype "open_collector"))
      (node (ref "JP22") (pin "4") (pinfunction "4_4") (pintype "passive"))
    )
    (net (code "90") (name "3B5") (class "Default")
      (node (ref "IC10") (pin "11") (pinfunction "OUT4_11") (pintype "open_collector"))
      (node (ref "JP22") (pin "5") (pinfunction "5_5") (pintype "passive"))
    )
    (net (code "91") (name "3B6") (class "Default")
      (node (ref "IC10") (pin "12") (pinfunction "OUT5_12") (pintype "open_collector"))
      (node (ref "JP22") (pin "6") (pinfunction "6_6") (pintype "passive"))
    )
    (net (code "92") (name "3B7") (class "Default")
      (node (ref "IC10") (pin "13") (pinfunction "OUT6_13") (pintype "open_collector"))
      (node (ref "JP22") (pin "7") (pinfunction "7_7") (pintype "passive"))
    )
    (net (code "93") (name "3B8") (class "Default")
      (node (ref "IC10") (pin "14") (pinfunction "OUT7_14") (pintype "open_collector"))
      (node (ref "JP22") (pin "8") (pinfunction "8_8") (pintype "passive"))
    )
    (net (code "94") (name "3B9") (class "Default")
      (node (ref "IC10") (pin "15") (pinfunction "OUT8_15") (pintype "open_collector"))
      (node (ref "JP23") (pin "1") (pinfunction "1_1") (pintype "passive"))
    )
    (net (code "95") (name "3B10") (class "Default")
      (node (ref "IC10") (pin "16") (pinfunction "OUT9_16") (pintype "open_collector"))
      (node (ref "JP23") (pin "2") (pinfunction "2_2") (pintype "passive"))
    )
    (net (code "96") (name "3B11") (class "Default")
      (node (ref "IC10") (pin "17") (pinfunction "OUT10_17") (pintype "open_collector"))
      (node (ref "JP23") (pin "3") (pinfunction "3_3") (pintype "passive"))
    )
    (net (code "97") (name "3B12") (class "Default")
      (node (ref "IC10") (pin "18") (pinfunction "OUT11_18") (pintype "open_collector"))
      (node (ref "JP23") (pin "4") (pinfunction "4_4") (pintype "passive"))
    )
    (net (code "98") (name "3B13") (class "Default")
      (node (ref "IC10") (pin "19") (pinfunction "OUT12_19") (pintype "open_collector"))
      (node (ref "JP23") (pin "5") (pinfunction "5_5") (pintype "passive"))
    )
    (net (code "99") (name "3B14") (class "Default")
      (node (ref "IC10") (pin "20") (pinfunction "OUT13_20") (pintype "open_collector"))
      (node (ref "JP23") (pin "6") (pinfunction "6_6") (pintype "passive"))
    )
    (net (code "100") (name "3B15") (class "Default")
      (node (ref "IC10") (pin "21") (pinfunction "OUT14_21") (pintype "open_collector"))
      (node (ref "JP23") (pin "7") (pinfunction "7_7") (pintype "passive"))
    )
    (net (code "101") (name "3B16") (class "Default")
      (node (ref "IC10") (pin "22") (pinfunction "OUT15_22") (pintype "open_collector"))
      (node (ref "JP23") (pin "8") (pinfunction "8_8") (pintype "passive"))
    )
    (net (code "102") (name "3C1") (class "Default")
      (node (ref "IC11") (pin "7") (pinfunction "OUT0_7") (pintype "open_collector"))
      (node (ref "JP24") (pin "1") (pinfunction "1_1") (pintype "passive"))
    )
    (net (code "103") (name "3C2") (class "Default")
      (node (ref "IC11") (pin "8") (pinfunction "OUT1_8") (pintype "open_collector"))
      (node (ref "JP24") (pin "2") (pinfunction "2_2") (pintype "passive"))
    )
    (net (code "104") (name "3C3") (class "Default")
      (node (ref "IC11") (pin "9") (pinfunction "OUT2_9") (pintype "open_collector"))
      (node (ref "JP24") (pin "3") (pinfunction "3_3") (pintype "passive"))
    )
    (net (code "105") (name "3C4") (class "Default")
      (node (ref "IC11") (pin "10") (pinfunction "OUT3_10") (pintype "open_collector"))
      (node (ref "JP24") (pin "4") (pinfunction "4_4") (pintype "passive"))
    )
    (net (code "106") (name "3C5") (class "Default")
      (node (ref "IC11") (pin "11") (pinfunction "OUT4_11") (pintype "open_collector"))
      (node (ref "JP24") (pin "5") (pinfunction "5_5") (pintype "passive"))
    )
    (net (code "107") (name "3C6") (class "Default")
      (node (ref "IC11") (pin "12") (pinfunction "OUT5_12") (pintype "open_collector"))
      (node (ref "JP24") (pin "6") (pinfunction "6_6") (pintype "passive"))
    )
    (net (code "108") (name "3C7") (class "Default")
      (node (ref "IC11") (pin "13") (pinfunction "OUT6_13") (pintype "open_collector"))
      (node (ref "JP24") (pin "7") (pinfunction "7_7") (pintype "passive"))
    )
    (net (code "109") (name "3C8") (class "Default")
      (node (ref "IC11") (pin "14") (pinfunction "OUT7_14") (pintype "open_collector"))
      (node (ref "JP24") (pin "8") (pinfunction "8_8") (pintype "passive"))
    )
    (net (code "110") (name "3C9") (class "Default")
      (node (ref "IC11") (pin "15") (pinfunction "OUT8_15") (pintype "open_collector"))
      (node (ref "JP25") (pin "1") (pinfunction "1_1") (pintype "passive"))
    )
    (net (code "111") (name "3C10") (class "Default")
      (node (ref "IC11") (pin "16") (pinfunction "OUT9_16") (pintype "open_collector"))
      (node (ref "JP25") (pin "2") (pinfunction "2_2") (pintype "passive"))
    )
    (net (code "112") (name "3C11") (class "Default")
      (node (ref "IC11") (pin "17") (pinfunction "OUT10_17") (pintype "open_collector"))
      (node (ref "JP25") (pin "3") (pinfunction "3_3") (pintype "passive"))
    )
    (net (code "113") (name "3C12") (class "Default")
      (node (ref "IC11") (pin "18") (pinfunction "OUT11_18") (pintype "open_collector"))
      (node (ref "JP25") (pin "4") (pinfunction "4_4") (pintype "passive"))
    )
    (net (code "114") (name "3C13") (class "Default")
      (node (ref "IC11") (pin "19") (pinfunction "OUT12_19") (pintype "open_collector"))
      (node (ref "JP25") (pin "5") (pinfunction "5_5") (pintype "passive"))
    )
    (net (code "115") (name "3C14") (class "Default")
      (node (ref "IC11") (pin "20") (pinfunction "OUT13_20") (pintype "open_collector"))
      (node (ref "JP25") (pin "6") (pinfunction "6_6") (pintype "passive"))
    )
    (net (code "116") (name "3C15") (class "Default")
      (node (ref "IC11") (pin "21") (pinfunction "OUT14_21") (pintype "open_collector"))
      (node (ref "JP25") (pin "7") (pinfunction "7_7") (pintype "passive"))
    )
    (net (code "117") (name "3C16") (class "Default")
      (node (ref "IC11") (pin "22") (pinfunction "OUT15_22") (pintype "open_collector"))
      (node (ref "JP25") (pin "8") (pinfunction "8_8") (pintype "passive"))
    )
    (net (code "118") (name "3D1") (class "Default")
      (node (ref "IC12") (pin "7") (pinfunction "OUT0_7") (pintype "open_collector"))
      (node (ref "JP26") (pin "1") (pinfunction "1_1") (pintype "passive"))
    )
    (net (code "119") (name "3D2") (class "Default")
      (node (ref "IC12") (pin "8") (pinfunction "OUT1_8") (pintype "open_collector"))
      (node (ref "JP26") (pin "2") (pinfunction "2_2") (pintype "passive"))
    )
    (net (code "120") (name "3D3") (class "Default")
      (node (ref "IC12") (pin "9") (pinfunction "OUT2_9") (pintype "open_collector"))
      (node (ref "JP26") (pin "3") (pinfunction "3_3") (pintype "passive"))
    )
    (net (code "121") (name "3D4") (class "Default")
      (node (ref "IC12") (pin "10") (pinfunction "OUT3_10") (pintype "open_collector"))
      (node (ref "JP26") (pin "4") (pinfunction "4_4") (pintype "passive"))
    )
    (net (code "122") (name "3D5") (class "Default")
      (node (ref "IC12") (pin "11") (pinfunction "OUT4_11") (pintype "open_collector"))
      (node (ref "JP26") (pin "5") (pinfunction "5_5") (pintype "passive"))
    )
    (net (code "123") (name "3D6") (class "Default")
      (node (ref "IC12") (pin "12") (pinfunction "OUT5_12") (pintype "open_collector"))
      (node (ref "JP26") (pin "6") (pinfunction "6_6") (pintype "passive"))
    )
    (net (code "124") (name "3D7") (class "Default")
      (node (ref "IC12") (pin "13") (pinfunction "OUT6_13") (pintype "open_collector"))
      (node (ref "JP26") (pin "7") (pinfunction "7_7") (pintype "passive"))
    )
    (net (code "125") (name "3D8") (class "Default")
      (node (ref "IC12") (pin "14") (pinfunction "OUT7_14") (pintype "open_collector"))
      (node (ref "JP26") (pin "8") (pinfunction "8_8") (pintype "passive"))
    )
    (net (code "126") (name "3D9") (class "Default")
      (node (ref "IC12") (pin "15") (pinfunction "OUT8_15") (pintype "open_collector"))
      (node (ref "JP27") (pin "1") (pinfunction "1_1") (pintype "passive"))
    )
    (net (code "127") (name "3D10") (class "Default")
      (node (ref "IC12") (pin "16") (pinfunction "OUT9_16") (pintype "open_collector"))
      (node (ref "JP27") (pin "2") (pinfunction "2_2") (pintype "passive"))
    )
    (net (code "128") (name "3D11") (class "Default")
      (node (ref "IC12") (pin "17") (pinfunction "OUT10_17") (pintype "open_collector"))
      (node (ref "JP27") (pin "3") (pinfunction "3_3") (pintype "passive"))
    )
    (net (code "129") (name "3D12") (class "Default")
      (node (ref "IC12") (pin "18") (pinfunction "OUT11_18") (pintype "open_collector"))
      (node (ref "JP27") (pin "4") (pinfunction "4_4") (pintype "passive"))
    )
    (net (code "130") (name "3D13") (class "Default")
      (node (ref "IC12") (pin "19") (pinfunction "OUT12_19") (pintype "open_collector"))
      (node (ref "JP27") (pin "5") (pinfunction "5_5") (pintype "passive"))
    )
    (net (code "131") (name "3D14") (class "Default")
      (node (ref "IC12") (pin "20") (pinfunction "OUT13_20") (pintype "open_collector"))
      (node (ref "JP27") (pin "6") (pinfunction "6_6") (pintype "passive"))
    )
    (net (code "132") (name "3D15") (class "Default")
      (node (ref "IC12") (pin "21") (pinfunction "OUT14_21") (pintype "open_collector"))
      (node (ref "JP27") (pin "7") (pinfunction "7_7") (pintype "passive"))
    )
    (net (code "133") (name "3D16") (class "Default")
      (node (ref "IC12") (pin "22") (pinfunction "OUT15_22") (pintype "open_collector"))
      (node (ref "JP27") (pin "8") (pinfunction "8_8") (pintype "passive"))
    )
    (net (code "134") (name "3SIN") (class "Default")
      (node (ref "IC8") (pin "24") (pinfunction "SOUT_24") (pintype "output"))
      (node (ref "IC9") (pin "5") (pinfunction "SIN_5") (pintype "input"))
    )
    (net (code "135") (name "3SIN_B") (class "Default")
      (node (ref "IC10") (pin "5") (pinfunction "SIN_5") (pintype "input"))
      (node (ref "IC9") (pin "24") (pinfunction "SOUT_24") (pintype "output"))
    )
    (net (code "136") (name "3SIN_C") (class "Default")
      (node (ref "IC10") (pin "24") (pinfunction "SOUT_24") (pintype "output"))
      (node (ref "IC11") (pin "5") (pinfunction "SIN_5") (pintype "input"))
    )
    (net (code "137") (name "3SIN_D") (class "Default")
      (node (ref "IC11") (pin "24") (pinfunction "SOUT_24") (pintype "output"))
      (node (ref "IC12") (pin "5") (pinfunction "SIN_5") (pintype "input"))
    )
    (net (code "138") (name "4SIN") (class "Default")
      (node (ref "IC12") (pin "24") (pinfunction "SOUT_24") (pintype "output"))
    )
    (net (code "139") (name "A1") (class "Default")
      (node (ref "IC1") (pin "7") (pinfunction "OUT0_7") (pintype "open_collector"))
      (node (ref "JP2") (pin "1") (pinfunction "1_1") (pintype "passive"))
    )
    (net (code "140") (name "A2") (class "Default")
      (node (ref "IC1") (pin "8") (pinfunction "OUT1_8") (pintype "open_collector"))
      (node (ref "JP2") (pin "2") (pinfunction "2_2") (pintype "passive"))
    )
    (net (code "141") (name "A3") (class "Default")
      (node (ref "IC1") (pin "9") (pinfunction "OUT2_9") (pintype "open_collector"))
      (node (ref "JP2") (pin "3") (pinfunction "3_3") (pintype "passive"))
    )
    (net (code "142") (name "A4") (class "Default")
      (node (ref "IC1") (pin "10") (pinfunction "OUT3_10") (pintype "open_collector"))
      (node (ref "JP2") (pin "4") (pinfunction "4_4") (pintype "passive"))
    )
    (net (code "143") (name "A5") (class "Default")
      (node (ref "IC1") (pin "11") (pinfunction "OUT4_11") (pintype "open_collector"))
      (node (ref "JP2") (pin "5") (pinfunction "5_5") (pintype "passive"))
    )
    (net (code "144") (name "A6") (class "Default")
      (node (ref "IC1") (pin "12") (pinfunction "OUT5_12") (pintype "open_collector"))
      (node (ref "JP2") (pin "6") (pinfunction "6_6") (pintype "passive"))
    )
    (net (code "145") (name "A7") (class "Default")
      (node (ref "IC1") (pin "13") (pinfunction "OUT6_13") (pintype "open_collector"))
      (node (ref "JP2") (pin "7") (pinfunction "7_7") (pintype "passive"))
    )
    (net (code "146") (name "A8") (class "Default")
      (node (ref "IC1") (pin "14") (pinfunction "OUT7_14") (pintype "open_collector"))
      (node (ref "JP2") (pin "8") (pinfunction "8_8") (pintype "passive"))
    )
    (net (code "147") (name "A9") (class "Default")
      (node (ref "IC1") (pin "15") (pinfunction "OUT8_15") (pintype "open_collector"))
      (node (ref "JP3") (pin "1") (pinfunction "1_1") (pintype "passive"))
    )
    (net (code "148") (name "A10") (class "Default")
      (node (ref "IC1") (pin "16") (pinfunction "OUT9_16") (pintype "open_collector"))
      (node (ref "JP3") (pin "2") (pinfunction "2_2") (pintype "passive"))
    )
    (net (code "149") (name "A11") (class "Default")
      (node (ref "IC1") (pin "17") (pinfunction "OUT10_17") (pintype "open_collector"))
      (node (ref "JP3") (pin "3") (pinfunction "3_3") (pintype "passive"))
    )
    (net (code "150") (name "A12") (class "Default")
      (node (ref "IC1") (pin "18") (pinfunction "OUT11_18") (pintype "open_collector"))
      (node (ref "JP3") (pin "4") (pinfunction "4_4") (pintype "passive"))
    )
    (net (code "151") (name "A13") (class "Default")
      (node (ref "IC1") (pin "19") (pinfunction "OUT12_19") (pintype "open_collector"))
      (node (ref "JP3") (pin "5") (pinfunction "5_5") (pintype "passive"))
    )
    (net (code "152") (name "A14") (class "Default")
      (node (ref "IC1") (pin "20") (pinfunction "OUT13_20") (pintype "open_collector"))
      (node (ref "JP3") (pin "6") (pinfunction "6_6") (pintype "passive"))
    )
    (net (code "153") (name "A15") (class "Default")
      (node (ref "IC1") (pin "21") (pinfunction "OUT14_21") (pintype "open_collector"))
      (node (ref "JP3") (pin "7") (pinfunction "7_7") (pintype "passive"))
    )
    (net (code "154") (name "A16") (class "Default")
      (node (ref "IC1") (pin "22") (pinfunction "OUT15_22") (pintype "open_collector"))
      (node (ref "JP3") (pin "8") (pinfunction "8_8") (pintype "passive"))
    )
    (net (code "155") (name "B1") (class "Default")
      (node (ref "IC2") (pin "7") (pinfunction "OUT0_7") (pintype "open_collector"))
      (node (ref "JP4") (pin "1") (pinfunction "1_1") (pintype "passive"))
    )
    (net (code "156") (name "B2") (class "Default")
      (node (ref "IC2") (pin "8") (pinfunction "OUT1_8") (pintype "open_collector"))
      (node (ref "JP4") (pin "2") (pinfunction "2_2") (pintype "passive"))
    )
    (net (code "157") (name "B3") (class "Default")
      (node (ref "IC2") (pin "9") (pinfunction "OUT2_9") (pintype "open_collector"))
      (node (ref "JP4") (pin "3") (pinfunction "3_3") (pintype "passive"))
    )
    (net (code "158") (name "B4") (class "Default")
      (node (ref "IC2") (pin "10") (pinfunction "OUT3_10") (pintype "open_collector"))
      (node (ref "JP4") (pin "4") (pinfunction "4_4") (pintype "passive"))
    )
    (net (code "159") (name "B5") (class "Default")
      (node (ref "IC2") (pin "11") (pinfunction "OUT4_11") (pintype "open_collector"))
      (node (ref "JP4") (pin "5") (pinfunction "5_5") (pintype "passive"))
    )
    (net (code "160") (name "B6") (class "Default")
      (node (ref "IC2") (pin "12") (pinfunction "OUT5_12") (pintype "open_collector"))
      (node (ref "JP4") (pin "6") (pinfunction "6_6") (pintype "passive"))
    )
    (net (code "161") (name "B7") (class "Default")
      (node (ref "IC2") (pin "13") (pinfunction "OUT6_13") (pintype "open_collector"))
      (node (ref "JP4") (pin "7") (pinfunction "7_7") (pintype "passive"))
    )
    (net (code "162") (name "B8") (class "Default")
      (node (ref "IC2") (pin "14") (pinfunction "OUT7_14") (pintype "open_collector"))
      (node (ref "JP4") (pin "8") (pinfunction "8_8") (pintype "passive"))
    )
    (net (code "163") (name "B9") (class "Default")
      (node (ref "IC2") (pin "15") (pinfunction "OUT8_15") (pintype "open_collector"))
      (node (ref "JP5") (pin "1") (pinfunction "1_1") (pintype "passive"))
    )
    (net (code "164") (name "B10") (class "Default")
      (node (ref "IC2") (pin "16") (pinfunction "OUT9_16") (pintype "open_collector"))
      (node (ref "JP5") (pin "2") (pinfunction "2_2") (pintype "passive"))
    )
    (net (code "165") (name "B11") (class "Default")
      (node (ref "IC2") (pin "17") (pinfunction "OUT10_17") (pintype "open_collector"))
      (node (ref "JP5") (pin "3") (pinfunction "3_3") (pintype "passive"))
    )
    (net (code "166") (name "B12") (class "Default")
      (node (ref "IC2") (pin "18") (pinfunction "OUT11_18") (pintype "open_collector"))
      (node (ref "JP5") (pin "4") (pinfunction "4_4") (pintype "passive"))
    )
    (net (code "167") (name "B13") (class "Default")
      (node (ref "IC2") (pin "19") (pinfunction "OUT12_19") (pintype "open_collector"))
      (node (ref "JP5") (pin "5") (pinfunction "5_5") (pintype "passive"))
    )
    (net (code "168") (name "B14") (class "Default")
      (node (ref "IC2") (pin "20") (pinfunction "OUT13_20") (pintype "open_collector"))
      (node (ref "JP5") (pin "6") (pinfunction "6_6") (pintype "passive"))
    )
    (net (code "169") (name "B15") (class "Default")
      (node (ref "IC2") (pin "21") (pinfunction "OUT14_21") (pintype "open_collector"))
      (node (ref "JP5") (pin "7") (pinfunction "7_7") (pintype "passive"))
    )
    (net (code "170") (name "B16") (class "Default")
      (node (ref "IC2") (pin "22") (pinfunction "OUT15_22") (pintype "open_collector"))
      (node (ref "JP5") (pin "8") (pinfunction "8_8") (pintype "passive"))
    )
    (net (code "171") (name "BLANK") (class "Default")
      (node (ref "IC1") (pin "2") (pinfunction "BLANK_2") (pintype "input"))
      (node (ref "IC10") (pin "2") (pinfunction "BLANK_2") (pintype "input"))
      (node (ref "IC11") (pin "2") (pinfunction "BLANK_2") (pintype "input"))
      (node (ref "IC12") (pin "2") (pinfunction "BLANK_2") (pintype "input"))
      (node (ref "IC2") (pin "2") (pinfunction "BLANK_2") (pintype "input"))
      (node (ref "IC3") (pin "2") (pinfunction "BLANK_2") (pintype "input"))
      (node (ref "IC4") (pin "2") (pinfunction "BLANK_2") (pintype "input"))
      (node (ref "IC5") (pin "2") (pinfunction "BLANK_2") (pintype "input"))
      (node (ref "IC6") (pin "2") (pinfunction "BLANK_2") (pintype "input"))
      (node (ref "IC7") (pin "2") (pinfunction "BLANK_2") (pintype "input"))
      (node (ref "IC8") (pin "2") (pinfunction "BLANK_2") (pintype "input"))
      (node (ref "IC9") (pin "2") (pinfunction "BLANK_2") (pintype "input"))
      (node (ref "JP1") (pin "1") (pinfunction "1_1") (pintype "passive"))
      (node (ref "LPC1") (pin "24") (pinfunction "24_24") (pintype "passive"))
    )
    (net (code "172") (name "C1") (class "Default")
      (node (ref "IC3") (pin "7") (pinfunction "OUT0_7") (pintype "open_collector"))
      (node (ref "JP8") (pin "1") (pinfunction "1_1") (pintype "passive"))
    )
    (net (code "173") (name "C2") (class "Default")
      (node (ref "IC3") (pin "8") (pinfunction "OUT1_8") (pintype "open_collector"))
      (node (ref "JP8") (pin "2") (pinfunction "2_2") (pintype "passive"))
    )
    (net (code "174") (name "C3") (class "Default")
      (node (ref "IC3") (pin "9") (pinfunction "OUT2_9") (pintype "open_collector"))
      (node (ref "JP8") (pin "3") (pinfunction "3_3") (pintype "passive"))
    )
    (net (code "175") (name "C4") (class "Default")
      (node (ref "IC3") (pin "10") (pinfunction "OUT3_10") (pintype "open_collector"))
      (node (ref "JP8") (pin "4") (pinfunction "4_4") (pintype "passive"))
    )
    (net (code "176") (name "C5") (class "Default")
      (node (ref "IC3") (pin "11") (pinfunction "OUT4_11") (pintype "open_collector"))
      (node (ref "JP8") (pin "5") (pinfunction "5_5") (pintype "passive"))
    )
    (net (code "177") (name "C6") (class "Default")
      (node (ref "IC3") (pin "12") (pinfunction "OUT5_12") (pintype "open_collector"))
      (node (ref "JP8") (pin "6") (pinfunction "6_6") (pintype "passive"))
    )
    (net (code "178") (name "C7") (class "Default")
      (node (ref "IC3") (pin "13") (pinfunction "OUT6_13") (pintype "open_collector"))
      (node (ref "JP8") (pin "7") (pinfunction "7_7") (pintype "passive"))
    )
    (net (code "179") (name "C8") (class "Default")
      (node (ref "IC3") (pin "14") (pinfunction "OUT7_14") (pintype "open_collector"))
      (node (ref "JP8") (pin "8") (pinfunction "8_8") (pintype "passive"))
    )
    (net (code "180") (name "C9") (class "Default")
      (node (ref "IC3") (pin "15") (pinfunction "OUT8_15") (pintype "open_collector"))
      (node (ref "JP9") (pin "1") (pinfunction "1_1") (pintype "passive"))
    )
    (net (code "181") (name "C10") (class "Default")
      (node (ref "IC3") (pin "16") (pinfunction "OUT9_16") (pintype "open_collector"))
      (node (ref "JP9") (pin "2") (pinfunction "2_2") (pintype "passive"))
    )
    (net (code "182") (name "C11") (class "Default")
      (node (ref "IC3") (pin "17") (pinfunction "OUT10_17") (pintype "open_collector"))
      (node (ref "JP9") (pin "3") (pinfunction "3_3") (pintype "passive"))
    )
    (net (code "183") (name "C12") (class "Default")
      (node (ref "IC3") (pin "18") (pinfunction "OUT11_18") (pintype "open_collector"))
      (node (ref "JP9") (pin "4") (pinfunction "4_4") (pintype "passive"))
    )
    (net (code "184") (name "C13") (class "Default")
      (node (ref "IC3") (pin "19") (pinfunction "OUT12_19") (pintype "open_collector"))
      (node (ref "JP9") (pin "5") (pinfunction "5_5") (pintype "passive"))
    )
    (net (code "185") (name "C14") (class "Default")
      (node (ref "IC3") (pin "20") (pinfunction "OUT13_20") (pintype "open_collector"))
      (node (ref "JP9") (pin "6") (pinfunction "6_6") (pintype "passive"))
    )
    (net (code "186") (name "C15") (class "Default")
      (node (ref "IC3") (pin "21") (pinfunction "OUT14_21") (pintype "open_collector"))
      (node (ref "JP9") (pin "7") (pinfunction "7_7") (pintype "passive"))
    )
    (net (code "187") (name "C16") (class "Default")
      (node (ref "IC3") (pin "22") (pinfunction "OUT15_22") (pintype "open_collector"))
      (node (ref "JP9") (pin "8") (pinfunction "8_8") (pintype "passive"))
    )
    (net (code "188") (name "D1") (class "Default")
      (node (ref "IC4") (pin "7") (pinfunction "OUT0_7") (pintype "open_collector"))
      (node (ref "JP10") (pin "1") (pinfunction "1_1") (pintype "passive"))
    )
    (net (code "189") (name "D2") (class "Default")
      (node (ref "IC4") (pin "8") (pinfunction "OUT1_8") (pintype "open_collector"))
      (node (ref "JP10") (pin "2") (pinfunction "2_2") (pintype "passive"))
    )
    (net (code "190") (name "D3") (class "Default")
      (node (ref "IC4") (pin "9") (pinfunction "OUT2_9") (pintype "open_collector"))
      (node (ref "JP10") (pin "3") (pinfunction "3_3") (pintype "passive"))
    )
    (net (code "191") (name "D4") (class "Default")
      (node (ref "IC4") (pin "10") (pinfunction "OUT3_10") (pintype "open_collector"))
      (node (ref "JP10") (pin "4") (pinfunction "4_4") (pintype "passive"))
    )
    (net (code "192") (name "D5") (class "Default")
      (node (ref "IC4") (pin "11") (pinfunction "OUT4_11") (pintype "open_collector"))
      (node (ref "JP10") (pin "5") (pinfunction "5_5") (pintype "passive"))
    )
    (net (code "193") (name "D6") (class "Default")
      (node (ref "IC4") (pin "12") (pinfunction "OUT5_12") (pintype "open_collector"))
      (node (ref "JP10") (pin "6") (pinfunction "6_6") (pintype "passive"))
    )
    (net (code "194") (name "D7") (class "Default")
      (node (ref "IC4") (pin "13") (pinfunction "OUT6_13") (pintype "open_collector"))
      (node (ref "JP10") (pin "7") (pinfunction "7_7") (pintype "passive"))
    )
    (net (code "195") (name "D8") (class "Default")
      (node (ref "IC4") (pin "14") (pinfunction "OUT7_14") (pintype "open_collector"))
      (node (ref "JP10") (pin "8") (pinfunction "8_8") (pintype "passive"))
    )
    (net (code "196") (name "D9") (class "Default")
      (node (ref "IC4") (pin "15") (pinfunction "OUT8_15") (pintype "open_collector"))
      (node (ref "JP11") (pin "1") (pinfunction "1_1") (pintype "passive"))
    )
    (net (code "197") (name "D10") (class "Default")
      (node (ref "IC4") (pin "16") (pinfunction "OUT9_16") (pintype "open_collector"))
      (node (ref "JP11") (pin "2") (pinfunction "2_2") (pintype "passive"))
    )
    (net (code "198") (name "D11") (class "Default")
      (node (ref "IC4") (pin "17") (pinfunction "OUT10_17") (pintype "open_collector"))
      (node (ref "JP11") (pin "3") (pinfunction "3_3") (pintype "passive"))
    )
    (net (code "199") (name "D12") (class "Default")
      (node (ref "IC4") (pin "18") (pinfunction "OUT11_18") (pintype "open_collector"))
      (node (ref "JP11") (pin "4") (pinfunction "4_4") (pintype "passive"))
    )
    (net (code "200") (name "D13") (class "Default")
      (node (ref "IC4") (pin "19") (pinfunction "OUT12_19") (pintype "open_collector"))
      (node (ref "JP11") (pin "5") (pinfunction "5_5") (pintype "passive"))
    )
    (net (code "201") (name "D14") (class "Default")
      (node (ref "IC4") (pin "20") (pinfunction "OUT13_20") (pintype "open_collector"))
      (node (ref "JP11") (pin "6") (pinfunction "6_6") (pintype "passive"))
    )
    (net (code "202") (name "D15") (class "Default")
      (node (ref "IC4") (pin "21") (pinfunction "OUT14_21") (pintype "open_collector"))
      (node (ref "JP11") (pin "7") (pinfunction "7_7") (pintype "passive"))
    )
    (net (code "203") (name "D16") (class "Default")
      (node (ref "IC4") (pin "22") (pinfunction "OUT15_22") (pintype "open_collector"))
      (node (ref "JP11") (pin "8") (pinfunction "8_8") (pintype "passive"))
    )
    (net (code "204") (name "DCPRG") (class "Default")
      (node (ref "IC1") (pin "26") (pinfunction "DCPRG_26") (pintype "input"))
      (node (ref "IC10") (pin "26") (pinfunction "DCPRG_26") (pintype "input"))
      (node (ref "IC11") (pin "26") (pinfunction "DCPRG_26") (pintype "input"))
      (node (ref "IC12") (pin "26") (pinfunction "DCPRG_26") (pintype "input"))
      (node (ref "IC2") (pin "26") (pinfunction "DCPRG_26") (pintype "input"))
      (node (ref "IC3") (pin "26") (pinfunction "DCPRG_26") (pintype "input"))
      (node (ref "IC4") (pin "26") (pinfunction "DCPRG_26") (pintype "input"))
      (node (ref "IC5") (pin "26") (pinfunction "DCPRG_26") (pintype "input"))
      (node (ref "IC6") (pin "26") (pinfunction "DCPRG_26") (pintype "input"))
      (node (ref "IC7") (pin "26") (pinfunction "DCPRG_26") (pintype "input"))
      (node (ref "IC8") (pin "26") (pinfunction "DCPRG_26") (pintype "input"))
      (node (ref "IC9") (pin "26") (pinfunction "DCPRG_26") (pintype "input"))
      (node (ref "JP1") (pin "9") (pinfunction "9_9") (pintype "passive"))
      (node (ref "LPC1") (pin "26") (pinfunction "26_26") (pintype "passive"))
    )
    (net (code "205") (name "GND") (class "Default")
      (node (ref "C1") (pin "1") (pinfunction "1_1") (pintype "passive"))
      (node (ref "C10") (pin "1") (pinfunction "1_1") (pintype "passive"))
      (node (ref "C11") (pin "1") (pinfunction "1_1") (pintype "passive"))
      (node (ref "C12") (pin "1") (pinfunction "1_1") (pintype "passive"))
      (node (ref "C2") (pin "1") (pinfunction "1_1") (pintype "passive"))
      (node (ref "C3") (pin "1") (pinfunction "1_1") (pintype "passive"))
      (node (ref "C4") (pin "1") (pinfunction "1_1") (pintype "passive"))
      (node (ref "C5") (pin "1") (pinfunction "1_1") (pintype "passive"))
      (node (ref "C6") (pin "1") (pinfunction "1_1") (pintype "passive"))
      (node (ref "C7") (pin "1") (pinfunction "1_1") (pintype "passive"))
      (node (ref "C8") (pin "1") (pinfunction "1_1") (pintype "passive"))
      (node (ref "C9") (pin "1") (pinfunction "1_1") (pintype "passive"))
      (node (ref "IC1") (pin "1") (pinfunction "GND_1") (pintype "power_in"))
      (node (ref "IC10") (pin "1") (pinfunction "GND_1") (pintype "power_in"))
      (node (ref "IC11") (pin "1") (pinfunction "GND_1") (pintype "power_in"))
      (node (ref "IC12") (pin "1") (pinfunction "GND_1") (pintype "power_in"))
      (node (ref "IC2") (pin "1") (pinfunction "GND_1") (pintype "power_in"))
      (node (ref "IC3") (pin "1") (pinfunction "GND_1") (pintype "power_in"))
      (node (ref "IC4") (pin "1") (pinfunction "GND_1") (pintype "power_in"))
      (node (ref "IC5") (pin "1") (pinfunction "GND_1") (pintype "power_in"))
      (node (ref "IC6") (pin "1") (pinfunction "GND_1") (pintype "power_in"))
      (node (ref "IC7") (pin "1") (pinfunction "GND_1") (pintype "power_in"))
      (node (ref "IC8") (pin "1") (pinfunction "GND_1") (pintype "power_in"))
      (node (ref "IC9") (pin "1") (pinfunction "GND_1") (pintype "power_in"))
      (node (ref "JP1") (pin "4") (pinfunction "4_4") (pintype "passive"))
      (node (ref "LPC1") (pin "1") (pinfunction "1_1") (pintype "passive"))
      (node (ref "R1") (pin "2") (pinfunction "2_2") (pintype "passive"))
      (node (ref "R10") (pin "2") (pinfunction "2_2") (pintype "passive"))
      (node (ref "R11") (pin "2") (pinfunction "2_2") (pintype "passive"))
      (node (ref "R12") (pin "2") (pinfunction "2_2") (pintype "passive"))
      (node (ref "R13") (pin "1") (pinfunction "1_1") (pintype "passive"))
      (node (ref "R14") (pin "1") (pinfunction "1_1") (pintype "passive"))
      (node (ref "R15") (pin "1") (pinfunction "1_1") (pintype "passive"))
      (node (ref "R16") (pin "1") (pinfunction "1_1") (pintype "passive"))
      (node (ref "R17") (pin "1") (pinfunction "1_1") (pintype "passive"))
      (node (ref "R18") (pin "1") (pinfunction "1_1") (pintype "passive"))
      (node (ref "R19") (pin "1") (pinfunction "1_1") (pintype "passive"))
      (node (ref "R2") (pin "2") (pinfunction "2_2") (pintype "passive"))
      (node (ref "R20") (pin "1") (pinfunction "1_1") (pintype "passive"))
      (node (ref "R21") (pin "1") (pinfunction "1_1") (pintype "passive"))
      (node (ref "R3") (pin "2") (pinfunction "2_2") (pintype "passive"))
      (node (ref "R4") (pin "2") (pinfunction "2_2") (pintype "passive"))
      (node (ref "R5") (pin "2") (pinfunction "2_2") (pintype "passive"))
      (node (ref "R6") (pin "2") (pinfunction "2_2") (pintype "passive"))
      (node (ref "R7") (pin "2") (pinfunction "2_2") (pintype "passive"))
      (node (ref "R8") (pin "2") (pinfunction "2_2") (pintype "passive"))
      (node (ref "R9") (pin "2") (pinfunction "2_2") (pintype "passive"))
    )
    (net (code "206") (name "GSCLK") (class "Default")
      (node (ref "IC1") (pin "25") (pinfunction "GSCLK_25") (pintype "input"))
      (node (ref "IC10") (pin "25") (pinfunction "GSCLK_25") (pintype "input"))
      (node (ref "IC11") (pin "25") (pinfunction "GSCLK_25") (pintype "input"))
      (node (ref "IC12") (pin "25") (pinfunction "GSCLK_25") (pintype "input"))
      (node (ref "IC2") (pin "25") (pinfunction "GSCLK_25") (pintype "input"))
      (node (ref "IC3") (pin "25") (pinfunction "GSCLK_25") (pintype "input"))
      (node (ref "IC4") (pin "25") (pinfunction "GSCLK_25") (pintype "input"))
      (node (ref "IC5") (pin "25") (pinfunction "GSCLK_25") (pintype "input"))
      (node (ref "IC6") (pin "25") (pinfunction "GSCLK_25") (pintype "input"))
      (node (ref "IC7") (pin "25") (pinfunction "GSCLK_25") (pintype "input"))
      (node (ref "IC8") (pin "25") (pinfunction "GSCLK_25") (pintype "input"))
      (node (ref "IC9") (pin "25") (pinfunction "GSCLK_25") (pintype "input"))
      (node (ref "JP1") (pin "2") (pinfunction "2_2") (pintype "passive"))
      (node (ref "LPC1") (pin "42") (pinfunction "42_42") (pintype "passive"))
    )
    (net (code "207") (name "L1") (class "Default")
      (node (ref "JP6") (pin "1") (pinfunction "1_1") (pintype "passive"))
      (node (ref "Q1") (pin "2") (pinfunction "D_2") (pintype "passive"))
      (node (ref "R14") (pin "2") (pinfunction "2_2") (pintype "passive"))
    )
    (net (code "208") (name "L2") (class "Default")
      (node (ref "JP6") (pin "2") (pinfunction "2_2") (pintype "passive"))
      (node (ref "Q3") (pin "2") (pinfunction "D_2") (pintype "passive"))
      (node (ref "R16") (pin "2") (pinfunction "2_2") (pintype "passive"))
    )
    (net (code "209") (name "L3") (class "Default")
      (node (ref "JP6") (pin "3") (pinfunction "3_3") (pintype "passive"))
      (node (ref "Q5") (pin "2") (pinfunction "D_2") (pintype "passive"))
      (node (ref "R18") (pin "2") (pinfunction "2_2") (pintype "passive"))
    )
    (net (code "210") (name "L4") (class "Default")
      (node (ref "JP6") (pin "4") (pinfunction "4_4") (pintype "passive"))
      (node (ref "Q7") (pin "2") (pinfunction "D_2") (pintype "passive"))
      (node (ref "R20") (pin "2") (pinfunction "2_2") (pintype "passive"))
    )
    (net (code "211") (name "L5") (class "Default")
      (node (ref "JP6") (pin "5") (pinfunction "5_5") (pintype "passive"))
      (node (ref "Q2") (pin "2") (pinfunction "D_2") (pintype "passive"))
      (node (ref "R15") (pin "2") (pinfunction "2_2") (pintype "passive"))
    )
    (net (code "212") (name "L6") (class "Default")
      (node (ref "JP6") (pin "6") (pinfunction "6_6") (pintype "passive"))
      (node (ref "Q4") (pin "2") (pinfunction "D_2") (pintype "passive"))
      (node (ref "R17") (pin "2") (pinfunction "2_2") (pintype "passive"))
    )
    (net (code "213") (name "L7") (class "Default")
      (node (ref "JP6") (pin "7") (pinfunction "7_7") (pintype "passive"))
      (node (ref "Q6") (pin "2") (pinfunction "D_2") (pintype "passive"))
      (node (ref "R19") (pin "2") (pinfunction "2_2") (pintype "passive"))
    )
    (net (code "214") (name "L8") (class "Default")
      (node (ref "JP6") (pin "8") (pinfunction "8_8") (pintype "passive"))
      (node (ref "Q8") (pin "2") (pinfunction "D_2") (pintype "passive"))
      (node (ref "R21") (pin "2") (pinfunction "2_2") (pintype "passive"))
    )
    (net (code "215") (name "LAYER1") (class "Default")
      (node (ref "LPC1") (pin "73") (pinfunction "73_73") (pintype "passive"))
      (node (ref "Q1") (pin "1") (pinfunction "G_1") (pintype "passive"))
    )
    (net (code "216") (name "LAYER2") (class "Default")
      (node (ref "LPC1") (pin "72") (pinfunction "72_72") (pintype "passive"))
      (node (ref "Q3") (pin "1") (pinfunction "G_1") (pintype "passive"))
    )
    (net (code "217") (name "LAYER3") (class "Default")
      (node (ref "LPC1") (pin "71") (pinfunction "71_71") (pintype "passive"))
      (node (ref "Q5") (pin "1") (pinfunction "G_1") (pintype "passive"))
    )
    (net (code "218") (name "LAYER4") (class "Default")
      (node (ref "LPC1") (pin "70") (pinfunction "70_70") (pintype "passive"))
      (node (ref "Q7") (pin "1") (pinfunction "G_1") (pintype "passive"))
    )
    (net (code "219") (name "LAYER5") (class "Default")
      (node (ref "LPC1") (pin "69") (pinfunction "69_69") (pintype "passive"))
      (node (ref "Q2") (pin "1") (pinfunction "G_1") (pintype "passive"))
    )
    (net (code "220") (name "LAYER6") (class "Default")
      (node (ref "LPC1") (pin "68") (pinfunction "68_68") (pintype "passive"))
      (node (ref "Q4") (pin "1") (pinfunction "G_1") (pintype "passive"))
    )
    (net (code "221") (name "LAYER7") (class "Default")
      (node (ref "LPC1") (pin "67") (pinfunction "67_67") (pintype "passive"))
      (node (ref "Q6") (pin "1") (pinfunction "G_1") (pintype "passive"))
    )
    (net (code "222") (name "LAYER8") (class "Default")
      (node (ref "LPC1") (pin "66") (pinfunction "66_66") (pintype "passive"))
      (node (ref "Q8") (pin "1") (pinfunction "G_1") (pintype "passive"))
    )
    (net (code "223") (name "Net-(IC1-IREF)") (class "Default")
      (node (ref "IC1") (pin "27") (pinfunction "IREF_27") (pintype "passive"))
      (node (ref "R1") (pin "1") (pinfunction "1_1") (pintype "passive"))
    )
    (net (code "224") (name "Net-(IC2-IREF)") (class "Default")
      (node (ref "IC2") (pin "27") (pinfunction "IREF_27") (pintype "passive"))
      (node (ref "R2") (pin "1") (pinfunction "1_1") (pintype "passive"))
    )
    (net (code "225") (name "Net-(IC3-IREF)") (class "Default")
      (node (ref "IC3") (pin "27") (pinfunction "IREF_27") (pintype "passive"))
      (node (ref "R3") (pin "1") (pinfunction "1_1") (pintype "passive"))
    )
    (net (code "226") (name "Net-(IC4-IREF)") (class "Default")
      (node (ref "IC4") (pin "27") (pinfunction "IREF_27") (pintype "passive"))
      (node (ref "R4") (pin "1") (pinfunction "1_1") (pintype "passive"))
    )
    (net (code "227") (name "Net-(IC5-IREF)") (class "Default")
      (node (ref "IC5") (pin "27") (pinfunction "IREF_27") (pintype "passive"))
      (node (ref "R5") (pin "1") (pinfunction "1_1") (pintype "passive"))
    )
    (net (code "228") (name "Net-(IC6-IREF)") (class "Default")
      (node (ref "IC6") (pin "27") (pinfunction "IREF_27") (pintype "passive"))
      (node (ref "R6") (pin "1") (pinfunction "1_1") (pintype "passive"))
    )
    (net (code "229") (name "Net-(IC7-IREF)") (class "Default")
      (node (ref "IC7") (pin "27") (pinfunction "IREF_27") (pintype "passive"))
      (node (ref "R7") (pin "1") (pinfunction "1_1") (pintype "passive"))
    )
    (net (code "230") (name "Net-(IC8-IREF)") (class "Default")
      (node (ref "IC8") (pin "27") (pinfunction "IREF_27") (pintype "passive"))
      (node (ref "R8") (pin "1") (pinfunction "1_1") (pintype "passive"))
    )
    (net (code "231") (name "Net-(IC9-IREF)") (class "Default")
      (node (ref "IC9") (pin "27") (pinfunction "IREF_27") (pintype "passive"))
      (node (ref "R9") (pin "1") (pinfunction "1_1") (pintype "passive"))
    )
    (net (code "232") (name "Net-(IC10-IREF)") (class "Default")
      (node (ref "IC10") (pin "27") (pinfunction "IREF_27") (pintype "passive"))
      (node (ref "R10") (pin "1") (pinfunction "1_1") (pintype "passive"))
    )
    (net (code "233") (name "Net-(IC11-IREF)") (class "Default")
      (node (ref "IC11") (pin "27") (pinfunction "IREF_27") (pintype "passive"))
      (node (ref "R11") (pin "1") (pinfunction "1_1") (pintype "passive"))
    )
    (net (code "234") (name "Net-(IC12-IREF)") (class "Default")
      (node (ref "IC12") (pin "27") (pinfunction "IREF_27") (pintype "passive"))
      (node (ref "R12") (pin "1") (pinfunction "1_1") (pintype "passive"))
    )
    (net (code "235") (name "RESET_N") (class "Default")
      (node (ref "C13") (pin "2") (pinfunction "2_2") (pintype "passive"))
      (node (ref "LPC1") (pin "4") (pinfunction "4_4") (pintype "passive"))
      (node (ref "R13") (pin "2") (pinfunction "2_2") (pintype "passive"))
      (node (ref "S1") (pin "4") (pinfunction "P1_4") (pintype "passive"))
    )
    (net (code "236") (name "SCLK") (class "Default")
      (node (ref "IC1") (pin "4") (pinfunction "SCLK_4") (pintype "input"))
      (node (ref "IC10") (pin "4") (pinfunction "SCLK_4") (pintype "input"))
      (node (ref "IC11") (pin "4") (pinfunction "SCLK_4") (pintype "input"))
      (node (ref "IC12") (pin "4") (pinfunction "SCLK_4") (pintype "input"))
      (node (ref "IC2") (pin "4") (pinfunction "SCLK_4") (pintype "input"))
      (node (ref "IC3") (pin "4") (pinfunction "SCLK_4") (pintype "input"))
      (node (ref "IC4") (pin "4") (pinfunction "SCLK_4") (pintype "input"))
      (node (ref "IC5") (pin "4") (pinfunction "SCLK_4") (pintype "input"))
      (node (ref "IC6") (pin "4") (pinfunction "SCLK_4") (pintype "input"))
      (node (ref "IC7") (pin "4") (pinfunction "SCLK_4") (pintype "input"))
      (node (ref "IC8") (pin "4") (pinfunction "SCLK_4") (pintype "input"))
      (node (ref "IC9") (pin "4") (pinfunction "SCLK_4") (pintype "input"))
      (node (ref "JP1") (pin "3") (pinfunction "3_3") (pintype "passive"))
      (node (ref "LPC1") (pin "11") (pinfunction "11_11") (pintype "passive"))
    )
    (net (code "237") (name "SIN") (class "Default")
      (node (ref "IC1") (pin "5") (pinfunction "SIN_5") (pintype "input"))
      (node (ref "JP1") (pin "5") (pinfunction "5_5") (pintype "passive"))
      (node (ref "LPC1") (pin "13") (pinfunction "13_13") (pintype "passive"))
    )
    (net (code "238") (name "SIN_B") (class "Default")
      (node (ref "IC1") (pin "24") (pinfunction "SOUT_24") (pintype "output"))
      (node (ref "IC2") (pin "5") (pinfunction "SIN_5") (pintype "input"))
    )
    (net (code "239") (name "SIN_C") (class "Default")
      (node (ref "IC2") (pin "24") (pinfunction "SOUT_24") (pintype "output"))
      (node (ref "IC3") (pin "5") (pinfunction "SIN_5") (pintype "input"))
    )
    (net (code "240") (name "SIN_D") (class "Default")
      (node (ref "IC3") (pin "24") (pinfunction "SOUT_24") (pintype "output"))
      (node (ref "IC4") (pin "5") (pinfunction "SIN_5") (pintype "input"))
    )
    (net (code "241") (name "VCC") (class "Default")
      (node (ref "C1") (pin "2") (pinfunction "2_2") (pintype "passive"))
      (node (ref "C10") (pin "2") (pinfunction "2_2") (pintype "passive"))
      (node (ref "C11") (pin "2") (pinfunction "2_2") (pintype "passive"))
      (node (ref "C12") (pin "2") (pinfunction "2_2") (pintype "passive"))
      (node (ref "C2") (pin "2") (pinfunction "2_2") (pintype "passive"))
      (node (ref "C3") (pin "2") (pinfunction "2_2") (pintype "passive"))
      (node (ref "C4") (pin "2") (pinfunction "2_2") (pintype "passive"))
      (node (ref "C5") (pin "2") (pinfunction "2_2") (pintype "passive"))
      (node (ref "C6") (pin "2") (pinfunction "2_2") (pintype "passive"))
      (node (ref "C7") (pin "2") (pinfunction "2_2") (pintype "passive"))
      (node (ref "C8") (pin "2") (pinfunction "2_2") (pintype "passive"))
      (node (ref "C9") (pin "2") (pinfunction "2_2") (pintype "passive"))
      (node (ref "IC1") (pin "28") (pinfunction "VCC_28") (pintype "power_in"))
      (node (ref "IC10") (pin "28") (pinfunction "VCC_28") (pintype "power_in"))
      (node (ref "IC11") (pin "28") (pinfunction "VCC_28") (pintype "power_in"))
      (node (ref "IC12") (pin "28") (pinfunction "VCC_28") (pintype "power_in"))
      (node (ref "IC2") (pin "28") (pinfunction "VCC_28") (pintype "power_in"))
      (node (ref "IC3") (pin "28") (pinfunction "VCC_28") (pintype "power_in"))
      (node (ref "IC4") (pin "28") (pinfunction "VCC_28") (pintype "power_in"))
      (node (ref "IC5") (pin "28") (pinfunction "VCC_28") (pintype "power_in"))
      (node (ref "IC6") (pin "28") (pinfunction "VCC_28") (pintype "power_in"))
      (node (ref "IC7") (pin "28") (pinfunction "VCC_28") (pintype "power_in"))
      (node (ref "IC8") (pin "28") (pinfunction "VCC_28") (pintype "power_in"))
      (node (ref "IC9") (pin "28") (pinfunction "VCC_28") (pintype "power_in"))
      (node (ref "JP1") (pin "6") (pinfunction "6_6") (pintype "passive"))
    )
    (net (code "242") (name "VIN") (class "Default")
      (node (ref "LPC1") (pin "2") (pinfunction "2_2") (pintype "passive"))
    )
    (net (code "243") (name "VPRG") (class "Default")
      (node (ref "IC1") (pin "6") (pinfunction "VPRG_6") (pintype "input"))
      (node (ref "IC10") (pin "6") (pinfunction "VPRG_6") (pintype "input"))
      (node (ref "IC11") (pin "6") (pinfunction "VPRG_6") (pintype "input"))
      (node (ref "IC12") (pin "6") (pinfunction "VPRG_6") (pintype "input"))
      (node (ref "IC2") (pin "6") (pinfunction "VPRG_6") (pintype "input"))
      (node (ref "IC3") (pin "6") (pinfunction "VPRG_6") (pintype "input"))
      (node (ref "IC4") (pin "6") (pinfunction "VPRG_6") (pintype "input"))
      (node (ref "IC5") (pin "6") (pinfunction "VPRG_6") (pintype "input"))
      (node (ref "IC6") (pin "6") (pinfunction "VPRG_6") (pintype "input"))
      (node (ref "IC7") (pin "6") (pinfunction "VPRG_6") (pintype "input"))
      (node (ref "IC8") (pin "6") (pinfunction "VPRG_6") (pintype "input"))
      (node (ref "IC9") (pin "6") (pinfunction "VPRG_6") (pintype "input"))
      (node (ref "JP1") (pin "10") (pinfunction "10_10") (pintype "passive"))
      (node (ref "LPC1") (pin "25") (pinfunction "25_25") (pintype "passive"))
    )
    (net (code "244") (name "XLAT") (class "Default")
      (node (ref "IC1") (pin "3") (pinfunction "XLAT_3") (pintype "input"))
      (node (ref "IC10") (pin "3") (pinfunction "XLAT_3") (pintype "input"))
      (node (ref "IC11") (pin "3") (pinfunction "XLAT_3") (pintype "input"))
      (node (ref "IC12") (pin "3") (pinfunction "XLAT_3") (pintype "input"))
      (node (ref "IC2") (pin "3") (pinfunction "XLAT_3") (pintype "input"))
      (node (ref "IC3") (pin "3") (pinfunction "XLAT_3") (pintype "input"))
      (node (ref "IC4") (pin "3") (pinfunction "XLAT_3") (pintype "input"))
      (node (ref "IC5") (pin "3") (pinfunction "XLAT_3") (pintype "input"))
      (node (ref "IC6") (pin "3") (pinfunction "XLAT_3") (pintype "input"))
      (node (ref "IC7") (pin "3") (pinfunction "XLAT_3") (pintype "input"))
      (node (ref "IC8") (pin "3") (pinfunction "XLAT_3") (pintype "input"))
      (node (ref "IC9") (pin "3") (pinfunction "XLAT_3") (pintype "input"))
      (node (ref "JP1") (pin "7") (pinfunction "7_7") (pintype "passive"))
      (node (ref "LPC1") (pin "23") (pinfunction "23_23") (pintype "passive"))
    )
    (net (code "245") (name "unconnected-(IC1-XERR-Pad23)") (class "Default")
      (node (ref "IC1") (pin "23") (pinfunction "XERR_23") (pintype "open_collector"))
    )
    (net (code "246") (name "unconnected-(IC2-XERR-Pad23)") (class "Default")
      (node (ref "IC2") (pin "23") (pinfunction "XERR_23") (pintype "open_collector"))
    )
    (net (code "247") (name "unconnected-(IC3-XERR-Pad23)") (class "Default")
      (node (ref "IC3") (pin "23") (pinfunction "XERR_23") (pintype "open_collector"))
    )
    (net (code "248") (name "unconnected-(IC4-XERR-Pad23)") (class "Default")
      (node (ref "IC4") (pin "23") (pinfunction "XERR_23") (pintype "open_collector"))
    )
    (net (code "249") (name "unconnected-(IC5-XERR-Pad23)") (class "Default")
      (node (ref "IC5") (pin "23") (pinfunction "XERR_23") (pintype "open_collector"))
    )
    (net (code "250") (name "unconnected-(IC6-XERR-Pad23)") (class "Default")
      (node (ref "IC6") (pin "23") (pinfunction "XERR_23") (pintype "open_collector"))
    )
    (net (code "251") (name "unconnected-(IC7-XERR-Pad23)") (class "Default")
      (node (ref "IC7") (pin "23") (pinfunction "XERR_23") (pintype "open_collector"))
    )
    (net (code "252") (name "unconnected-(IC8-XERR-Pad23)") (class "Default")
      (node (ref "IC8") (pin "23") (pinfunction "XERR_23") (pintype "open_collector"))
    )
    (net (code "253") (name "unconnected-(IC9-XERR-Pad23)") (class "Default")
      (node (ref "IC9") (pin "23") (pinfunction "XERR_23") (pintype "open_collector"))
    )
    (net (code "254") (name "unconnected-(IC10-XERR-Pad23)") (class "Default")
      (node (ref "IC10") (pin "23") (pinfunction "XERR_23") (pintype "open_collector"))
    )
    (net (code "255") (name "unconnected-(IC11-XERR-Pad23)") (class "Default")
      (node (ref "IC11") (pin "23") (pinfunction "XERR_23") (pintype "open_collector"))
    )
    (net (code "256") (name "unconnected-(IC12-XERR-Pad23)") (class "Default")
      (node (ref "IC12") (pin "23") (pinfunction "XERR_23") (pintype "open_collector"))
    )
    (net (code "257") (name "unconnected-(JP1-Pad11)") (class "Default")
      (node (ref "JP1") (pin "11") (pinfunction "11_11") (pintype "passive"))
    )
    (net (code "258") (name "unconnected-(JP1-Pad12)") (class "Default")
      (node (ref "JP1") (pin "12") (pinfunction "12_12") (pintype "passive"))
    )
    (net (code "259") (name "unconnected-(LPC1-Pad3)") (class "Default")
      (node (ref "LPC1") (pin "3") (pinfunction "3_3") (pintype "passive"))
    )
    (net (code "260") (name "unconnected-(LPC1-Pad5)") (class "Default")
      (node (ref "LPC1") (pin "5") (pinfunction "5_5") (pintype "passive"))
    )
    (net (code "261") (name "unconnected-(LPC1-Pad6)") (class "Default")
      (node (ref "LPC1") (pin "6") (pinfunction "6_6") (pintype "passive"))
    )
    (net (code "262") (name "unconnected-(LPC1-Pad7)") (class "Default")
      (node (ref "LPC1") (pin "7") (pinfunction "7_7") (pintype "passive"))
    )
    (net (code "263") (name "unconnected-(LPC1-Pad8)") (class "Default")
      (node (ref "LPC1") (pin "8") (pinfunction "8_8") (pintype "passive"))
    )
    (net (code "264") (name "unconnected-(LPC1-Pad9)") (class "Default")
      (node (ref "LPC1") (pin "9") (pinfunction "9_9") (pintype "passive"))
    )
    (net (code "265") (name "unconnected-(LPC1-Pad10)") (class "Default")
      (node (ref "LPC1") (pin "10") (pinfunction "10_10") (pintype "passive"))
    )
    (net (code "266") (name "unconnected-(LPC1-Pad12)") (class "Default")
      (node (ref "LPC1") (pin "12") (pinfunction "12_12") (pintype "passive"))
    )
    (net (code "267") (name "unconnected-(LPC1-Pad14)") (class "Default")
      (node (ref "LPC1") (pin "14") (pinfunction "14_14") (pintype "passive"))
    )
    (net (code "268") (name "unconnected-(LPC1-Pad15)") (class "Default")
      (node (ref "LPC1") (pin "15") (pinfunction "15_15") (pintype "passive"))
    )
    (net (code "269") (name "unconnected-(LPC1-Pad16)") (class "Default")
      (node (ref "LPC1") (pin "16") (pinfunction "16_16") (pintype "passive"))
    )
    (net (code "270") (name "unconnected-(LPC1-Pad17)") (class "Default")
      (node (ref "LPC1") (pin "17") (pinfunction "17_17") (pintype "passive"))
    )
    (net (code "271") (name "unconnected-(LPC1-Pad18)") (class "Default")
      (node (ref "LPC1") (pin "18") (pinfunction "18_18") (pintype "passive"))
    )
    (net (code "272") (name "unconnected-(LPC1-Pad19)") (class "Default")
      (node (ref "LPC1") (pin "19") (pinfunction "19_19") (pintype "passive"))
    )
    (net (code "273") (name "unconnected-(LPC1-Pad20)") (class "Default")
      (node (ref "LPC1") (pin "20") (pinfunction "20_20") (pintype "passive"))
    )
    (net (code "274") (name "unconnected-(LPC1-Pad21)") (class "Default")
      (node (ref "LPC1") (pin "21") (pinfunction "21_21") (pintype "passive"))
    )
    (net (code "275") (name "unconnected-(LPC1-Pad22)") (class "Default")
      (node (ref "LPC1") (pin "22") (pinfunction "22_22") (pintype "passive"))
    )
    (net (code "276") (name "unconnected-(LPC1-Pad27)") (class "Default")
      (node (ref "LPC1") (pin "27") (pinfunction "27_27") (pintype "passive"))
    )
    (net (code "277") (name "unconnected-(LPC1-Pad29)") (class "Default")
      (node (ref "LPC1") (pin "29") (pinfunction "29_29") (pintype "passive"))
    )
    (net (code "278") (name "unconnected-(LPC1-Pad30)") (class "Default")
      (node (ref "LPC1") (pin "30") (pinfunction "30_30") (pintype "passive"))
    )
    (net (code "279") (name "unconnected-(LPC1-Pad31)") (class "Default")
      (node (ref "LPC1") (pin "31") (pinfunction "31_31") (pintype "passive"))
    )
    (net (code "280") (name "unconnected-(LPC1-Pad32)") (class "Default")
      (node (ref "LPC1") (pin "32") (pinfunction "32_32") (pintype "passive"))
    )
    (net (code "281") (name "unconnected-(LPC1-Pad33)") (class "Default")
      (node (ref "LPC1") (pin "33") (pinfunction "33_33") (pintype "passive"))
    )
    (net (code "282") (name "unconnected-(LPC1-Pad34)") (class "Default")
      (node (ref "LPC1") (pin "34") (pinfunction "34_34") (pintype "passive"))
    )
    (net (code "283") (name "unconnected-(LPC1-Pad35)") (class "Default")
      (node (ref "LPC1") (pin "35") (pinfunction "35_35") (pintype "passive"))
    )
    (net (code "284") (name "unconnected-(LPC1-Pad36)") (class "Default")
      (node (ref "LPC1") (pin "36") (pinfunction "36_36") (pintype "passive"))
    )
    (net (code "285") (name "unconnected-(LPC1-Pad37)") (class "Default")
      (node (ref "LPC1") (pin "37") (pinfunction "37_37") (pintype "passive"))
    )
    (net (code "286") (name "unconnected-(LPC1-Pad38)") (class "Default")
      (node (ref "LPC1") (pin "38") (pinfunction "38_38") (pintype "passive"))
    )
    (net (code "287") (name "unconnected-(LPC1-Pad39)") (class "Default")
      (node (ref "LPC1") (pin "39") (pinfunction "39_39") (pintype "passive"))
    )
    (net (code "288") (name "unconnected-(LPC1-Pad40)") (class "Default")
      (node (ref "LPC1") (pin "40") (pinfunction "40_40") (pintype "passive"))
    )
    (net (code "289") (name "unconnected-(LPC1-Pad41)") (class "Default")
      (node (ref "LPC1") (pin "41") (pinfunction "41_41") (pintype "passive"))
    )
    (net (code "290") (name "unconnected-(LPC1-Pad43)") (class "Default")
      (node (ref "LPC1") (pin "43") (pinfunction "43_43") (pintype "passive"))
    )
    (net (code "291") (name "unconnected-(LPC1-Pad44)") (class "Default")
      (node (ref "LPC1") (pin "44") (pinfunction "44_44") (pintype "passive"))
    )
    (net (code "292") (name "unconnected-(LPC1-Pad45)") (class "Default")
      (node (ref "LPC1") (pin "45") (pinfunction "45_45") (pintype "passive"))
    )
    (net (code "293") (name "unconnected-(LPC1-Pad46)") (class "Default")
      (node (ref "LPC1") (pin "46") (pinfunction "46_46") (pintype "passive"))
    )
    (net (code "294") (name "unconnected-(LPC1-Pad47)") (class "Default")
      (node (ref "LPC1") (pin "47") (pinfunction "47_47") (pintype "passive"))
    )
    (net (code "295") (name "unconnected-(LPC1-Pad48)") (class "Default")
      (node (ref "LPC1") (pin "48") (pinfunction "48_48") (pintype "passive"))
    )
    (net (code "296") (name "unconnected-(LPC1-Pad49)") (class "Default")
      (node (ref "LPC1") (pin "49") (pinfunction "49_49") (pintype "passive"))
    )
    (net (code "297") (name "unconnected-(LPC1-Pad50)") (class "Default")
      (node (ref "LPC1") (pin "50") (pinfunction "50_50") (pintype "passive"))
    )
    (net (code "298") (name "unconnected-(LPC1-Pad51)") (class "Default")
      (node (ref "LPC1") (pin "51") (pinfunction "51_51") (pintype "passive"))
    )
    (net (code "299") (name "unconnected-(LPC1-Pad52)") (class "Default")
      (node (ref "LPC1") (pin "52") (pinfunction "52_52") (pintype "passive"))
    )
    (net (code "300") (name "unconnected-(LPC1-Pad53)") (class "Default")
      (node (ref "LPC1") (pin "53") (pinfunction "53_53") (pintype "passive"))
    )
    (net (code "301") (name "unconnected-(LPC1-Pad54)") (class "Default")
      (node (ref "LPC1") (pin "54") (pinfunction "54_54") (pintype "passive"))
    )
    (net (code "302") (name "unconnected-(LPC1-Pad55)") (class "Default")
      (node (ref "LPC1") (pin "55") (pinfunction "55_55") (pintype "passive"))
    )
    (net (code "303") (name "unconnected-(LPC1-Pad56)") (class "Default")
      (node (ref "LPC1") (pin "56") (pinfunction "56_56") (pintype "passive"))
    )
    (net (code "304") (name "unconnected-(LPC1-Pad57)") (class "Default")
      (node (ref "LPC1") (pin "57") (pinfunction "57_57") (pintype "passive"))
    )
    (net (code "305") (name "unconnected-(LPC1-Pad58)") (class "Default")
      (node (ref "LPC1") (pin "58") (pinfunction "58_58") (pintype "passive"))
    )
    (net (code "306") (name "unconnected-(LPC1-Pad59)") (class "Default")
      (node (ref "LPC1") (pin "59") (pinfunction "59_59") (pintype "passive"))
    )
    (net (code "307") (name "unconnected-(LPC1-Pad60)") (class "Default")
      (node (ref "LPC1") (pin "60") (pinfunction "60_60") (pintype "passive"))
    )
    (net (code "308") (name "unconnected-(LPC1-Pad61)") (class "Default")
      (node (ref "LPC1") (pin "61") (pinfunction "61_61") (pintype "passive"))
    )
    (net (code "309") (name "unconnected-(LPC1-Pad62)") (class "Default")
      (node (ref "LPC1") (pin "62") (pinfunction "62_62") (pintype "passive"))
    )
    (net (code "310") (name "unconnected-(LPC1-Pad63)") (class "Default")
      (node (ref "LPC1") (pin "63") (pinfunction "63_63") (pintype "passive"))
    )
    (net (code "311") (name "unconnected-(LPC1-Pad64)") (class "Default")
      (node (ref "LPC1") (pin "64") (pinfunction "64_64") (pintype "passive"))
    )
    (net (code "312") (name "unconnected-(LPC1-Pad65)") (class "Default")
      (node (ref "LPC1") (pin "65") (pinfunction "65_65") (pintype "passive"))
    )
    (net (code "313") (name "unconnected-(Q1-S-Pad3)") (class "Default")
      (node (ref "Q1") (pin "3") (pinfunction "S_3") (pintype "passive"))
    )
    (net (code "314") (name "unconnected-(Q2-S-Pad3)") (class "Default")
      (node (ref "Q2") (pin "3") (pinfunction "S_3") (pintype "passive"))
    )
    (net (code "315") (name "unconnected-(Q3-S-Pad3)") (class "Default")
      (node (ref "Q3") (pin "3") (pinfunction "S_3") (pintype "passive"))
    )
    (net (code "316") (name "unconnected-(Q4-S-Pad3)") (class "Default")
      (node (ref "Q4") (pin "3") (pinfunction "S_3") (pintype "passive"))
    )
    (net (code "317") (name "unconnected-(Q5-S-Pad3)") (class "Default")
      (node (ref "Q5") (pin "3") (pinfunction "S_3") (pintype "passive"))
    )
    (net (code "318") (name "unconnected-(Q6-S-Pad3)") (class "Default")
      (node (ref "Q6") (pin "3") (pinfunction "S_3") (pintype "passive"))
    )
    (net (code "319") (name "unconnected-(Q7-S-Pad3)") (class "Default")
      (node (ref "Q7") (pin "3") (pinfunction "S_3") (pintype "passive"))
    )
    (net (code "320") (name "unconnected-(Q8-S-Pad3)") (class "Default")
      (node (ref "Q8") (pin "3") (pinfunction "S_3") (pintype "passive"))
    )
    (net (code "321") (name "unconnected-(S1-P-Pad3)") (class "Default")
      (node (ref "S1") (pin "3") (pinfunction "P_3") (pintype "passive"))
    )
    (net (code "322") (name "unconnected-(S1-S1-Pad2)") (class "Default")
      (node (ref "S1") (pin "2") (pinfunction "S1_2") (pintype "passive"))
    )
  )
)
